# HEXCORE_Schematic.net
KiCad netlist of a schematic drawn in Altium Designer
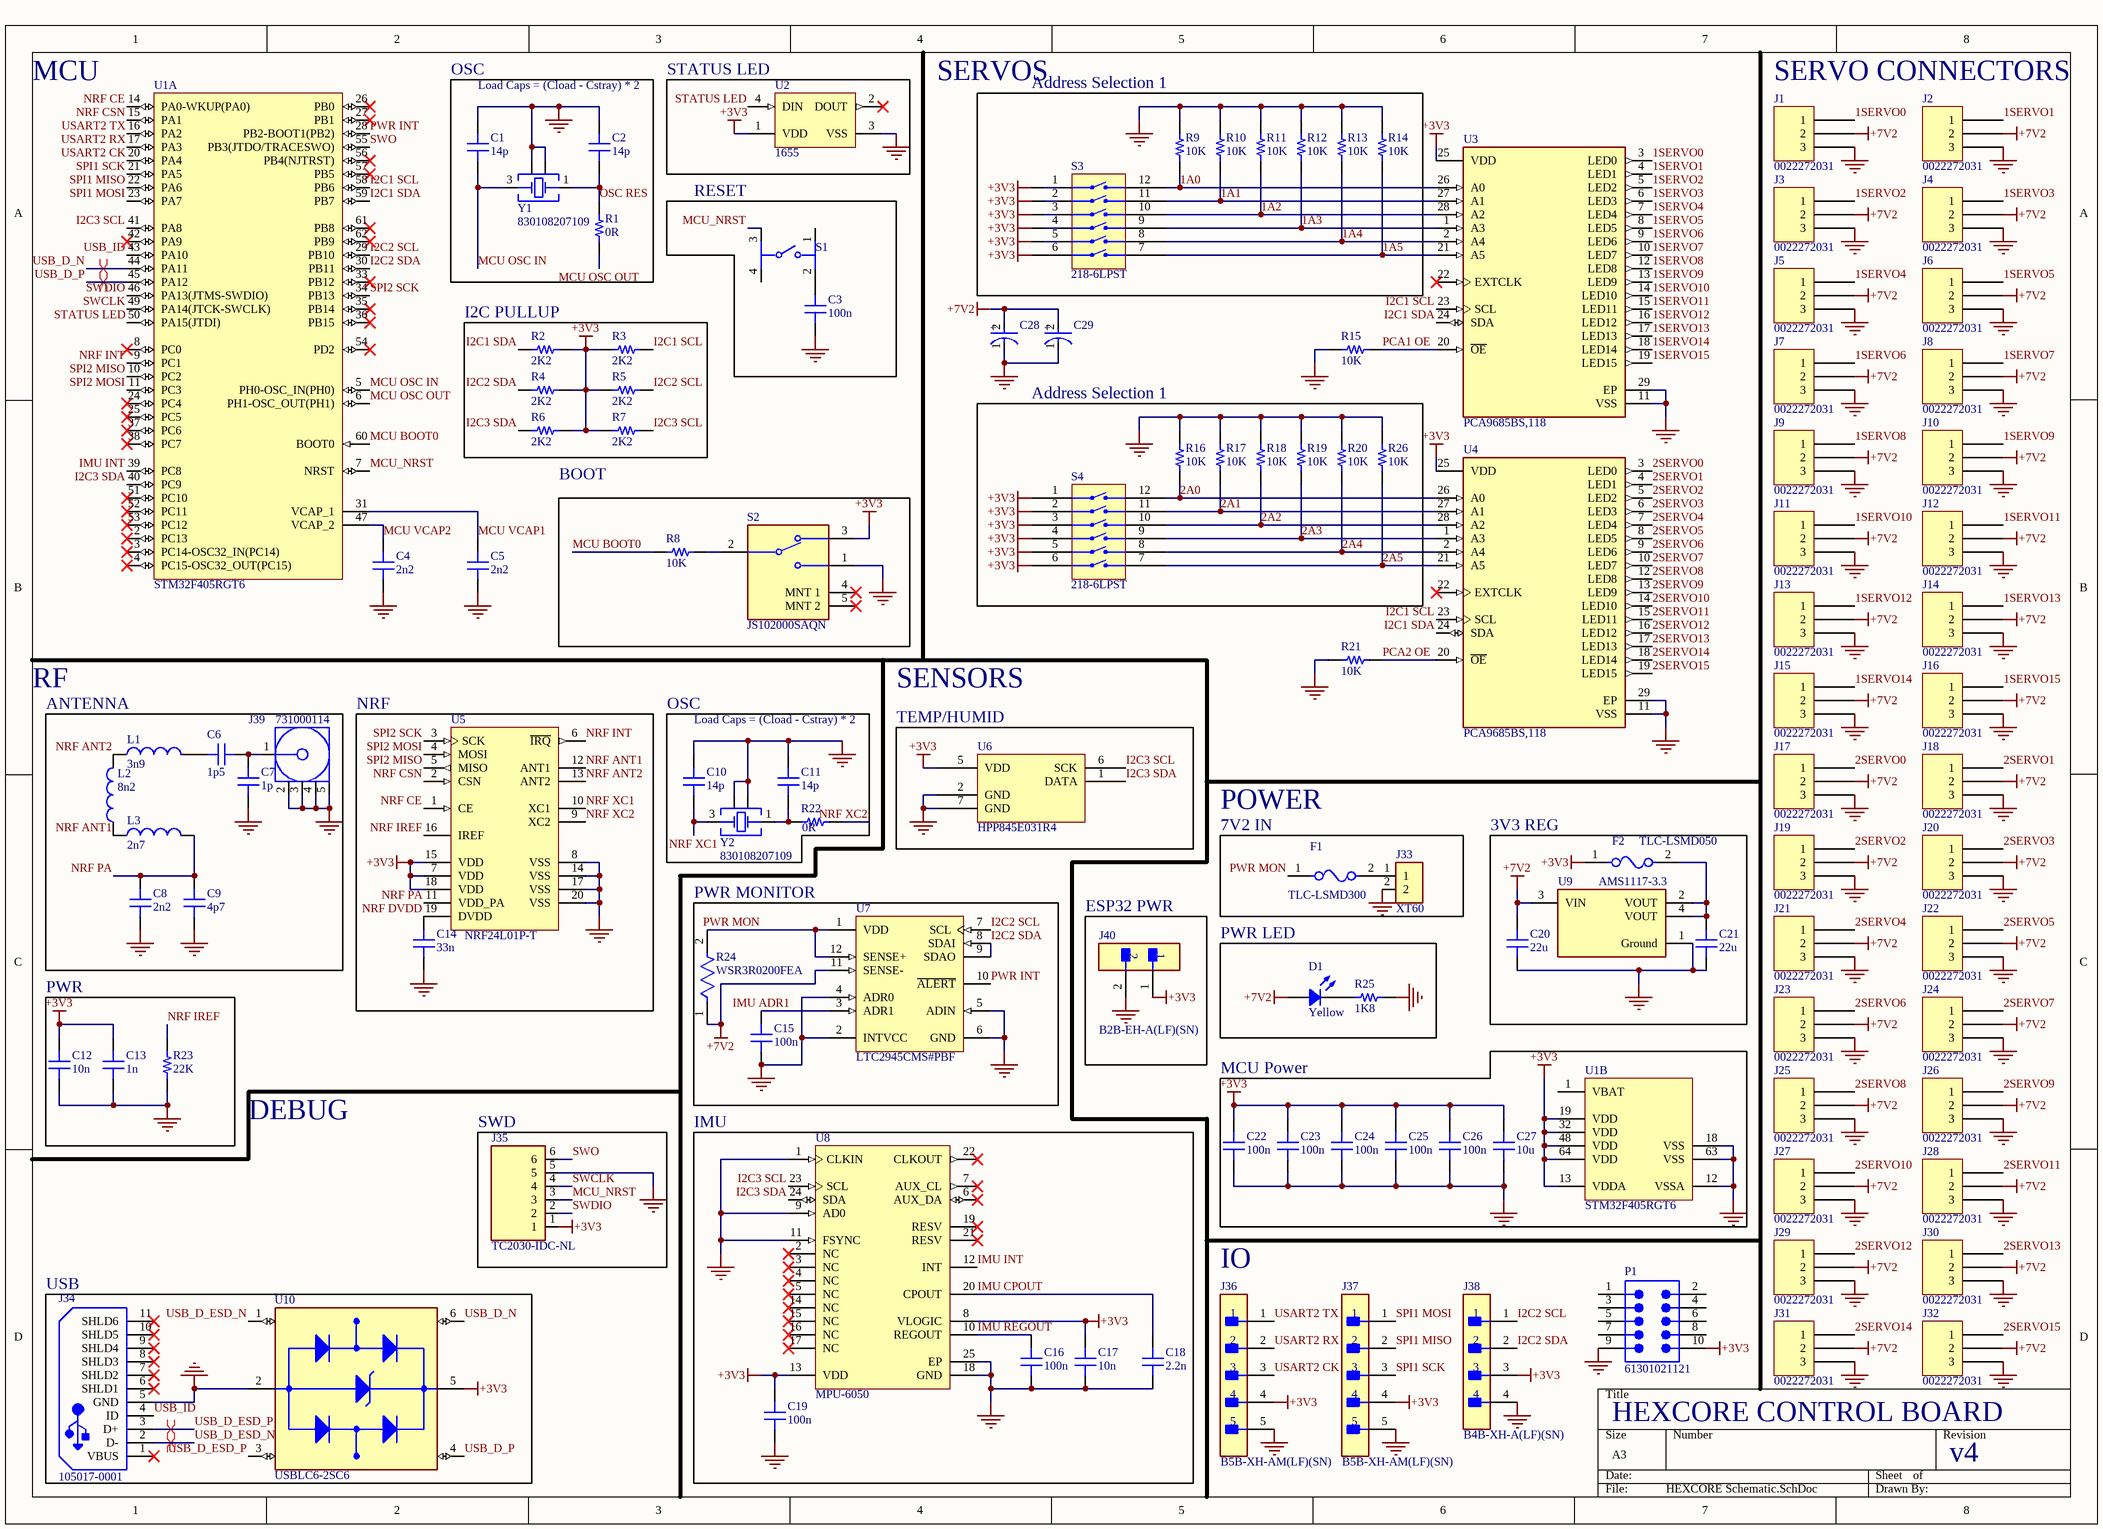
[diagram p0: HEXCORE Schematic.SchDoc]

(export (version "E")
  (design (tool "Eeschema 10.0.6"))
  (components
    (comp (ref "C1")
      (value "14p")
      (footprint "CAP 0402_1005")
      (description "CAP CER 14PF 50V C0G/NP0 0402")
      (fields (field (name "PART NUMBER") "GJM1555C1H140GB01D"))
      (libsource (lib "Celestial Altium Library - altium_library") (part "Capacitor"))
    )
    (comp (ref "C2")
      (value "14p")
      (footprint "CAP 0402_1005")
      (description "CAP CER 14PF 50V C0G/NP0 0402")
      (fields (field (name "PART NUMBER") "GJM1555C1H140GB01D"))
      (libsource (lib "Celestial Altium Library - altium_library") (part "Capacitor"))
    )
    (comp (ref "C3")
      (value "100n")
      (footprint "CAP 0402_1005")
      (description "CAP CER 100NF 10V X7R 0402")
      (fields (field (name "PART NUMBER") "CL05B104KP5VPNC"))
      (libsource (lib "Celestial Altium Library - altium_library") (part "Capacitor"))
    )
    (comp (ref "C4")
      (value "2n2")
      (footprint "CAP 0402_1005")
      (description "CAP CER 0402 2.2NF 25V C0G 5%")
      (fields (field (name "PART NUMBER") "C0402C222J3GEC7867"))
      (libsource (lib "Celestial Altium Library - altium_library") (part "Capacitor"))
    )
    (comp (ref "C5")
      (value "2n2")
      (footprint "CAP 0402_1005")
      (description "CAP CER 0402 2.2NF 25V C0G 5%")
      (fields (field (name "PART NUMBER") "C0402C222J3GEC7867"))
      (libsource (lib "Celestial Altium Library - altium_library") (part "Capacitor"))
    )
    (comp (ref "C6")
      (value "1p5")
      (footprint "CAP 0402_1005")
      (description "CAP CER 0402 10NF 16V X7R 10%")
      (fields (field (name "PART NUMBER") "C0402C103K4REC7867") (field (name "MANUFACTURER") "KEMET"))
      (libsource (lib "Celestial Altium Library - altium_library") (part "Capacitor"))
    )
    (comp (ref "C7")
      (value "1p")
      (footprint "CAP 0402_1005")
      (description "CAP CER 0402 10NF 16V X7R 10%")
      (fields (field (name "PART NUMBER") "C0402C103K4REC7867") (field (name "MANUFACTURER") "KEMET"))
      (libsource (lib "Celestial Altium Library - altium_library") (part "Capacitor"))
    )
    (comp (ref "C8")
      (value "2n2")
      (footprint "CAP 0402_1005")
      (description "CAP CER 0402 10NF 16V X7R 10%")
      (fields (field (name "PART NUMBER") "C0402C103K4REC7867") (field (name "MANUFACTURER") "KEMET"))
      (libsource (lib "Celestial Altium Library - altium_library") (part "Capacitor"))
    )
    (comp (ref "C9")
      (value "4p7")
      (footprint "CAP 0402_1005")
      (description "CAP CER 0402 10NF 16V X7R 10%")
      (fields (field (name "PART NUMBER") "C0402C103K4REC7867") (field (name "MANUFACTURER") "KEMET"))
      (libsource (lib "Celestial Altium Library - altium_library") (part "Capacitor"))
    )
    (comp (ref "C10")
      (value "14p")
      (footprint "CAP 0402_1005")
      (description "CAP CER 14PF 50V C0G/NP0 0402")
      (fields (field (name "PART NUMBER") "GJM1555C1H140GB01D"))
      (libsource (lib "Celestial Altium Library - altium_library") (part "Capacitor"))
    )
    (comp (ref "C11")
      (value "14p")
      (footprint "CAP 0402_1005")
      (description "CAP CER 14PF 50V C0G/NP0 0402")
      (fields (field (name "PART NUMBER") "GJM1555C1H140GB01D"))
      (libsource (lib "Celestial Altium Library - altium_library") (part "Capacitor"))
    )
    (comp (ref "C12")
      (value "10n")
      (footprint "CAP 0402_1005")
      (description "CAP CER 0402 10NF 16V X7R 10%")
      (fields (field (name "PART NUMBER") "C0402C103K4REC7867") (field (name "MANUFACTURER") "KEMET"))
      (libsource (lib "Celestial Altium Library - altium_library") (part "Capacitor"))
    )
    (comp (ref "C13")
      (value "1n")
      (footprint "CAP 0402_1005")
      (description "CAP CER 0402 10NF 16V X7R 10%")
      (fields (field (name "PART NUMBER") "C0402C103K4REC7867") (field (name "MANUFACTURER") "KEMET"))
      (libsource (lib "Celestial Altium Library - altium_library") (part "Capacitor"))
    )
    (comp (ref "C14")
      (value "33n")
      (footprint "CAP 0402_1005")
      (description "CAP CER 33PF 16V X7R 0402")
      (fields (field (name "PART NUMBER") "C0402C330J4RACAUTO") (field (name "MANUFACTURER") "KEMET"))
      (libsource (lib "Celestial Altium Library - altium_library") (part "Capacitor"))
    )
    (comp (ref "C15")
      (value "100n")
      (footprint "CAP 0402_1005")
      (description "CAP CER 100NF 10V X7R 0402")
      (fields (field (name "PART NUMBER") "CL05B104KP5VPNC"))
      (libsource (lib "Celestial Altium Library - altium_library") (part "Capacitor"))
    )
    (comp (ref "C16")
      (value "100n")
      (footprint "CAP 0402_1005")
      (description "CAP CER 100NF 10V X7R 0402")
      (fields (field (name "PART NUMBER") "CL05B104KP5VPNC"))
      (libsource (lib "Celestial Altium Library - altium_library") (part "Capacitor"))
    )
    (comp (ref "C17")
      (value "10n")
      (footprint "CAP 0402_1005")
      (description "CAP CER 0402 10NF 50V X7R 5%")
      (fields (field (name "PART NUMBER") "C0402C103J5RECAUTO"))
      (libsource (lib "Celestial Altium Library - altium_library") (part "Capacitor"))
    )
    (comp (ref "C18")
      (value "2.2n")
      (footprint "CAP 0402_1005")
      (description "CAP CER 0402 2.2NF 25V C0G 5%")
      (fields (field (name "PART NUMBER") "C0402C222J3GEC7867"))
      (libsource (lib "Celestial Altium Library - altium_library") (part "Capacitor"))
    )
    (comp (ref "C19")
      (value "100n")
      (footprint "CAP 0402_1005")
      (description "CAP CER 100NF 10V X7R 0402")
      (fields (field (name "PART NUMBER") "CL05B104KP5VPNC"))
      (libsource (lib "Celestial Altium Library - altium_library") (part "Capacitor"))
    )
    (comp (ref "C20")
      (value "22u")
      (footprint "CAP 0603_1608")
      (description "CAP CER 22UF 10V X5R 0603")
      (fields (field (name "PART NUMBER") "CL10A226MPCNUBE"))
      (libsource (lib "Celestial Altium Library - altium_library") (part "Capacitor"))
    )
    (comp (ref "C21")
      (value "22u")
      (footprint "CAP 0603_1608")
      (description "CAP CER 22UF 10V X5R 0603")
      (fields (field (name "PART NUMBER") "CL10A226MPCNUBE"))
      (libsource (lib "Celestial Altium Library - altium_library") (part "Capacitor"))
    )
    (comp (ref "C22")
      (value "100n")
      (footprint "CAP 0402_1005")
      (description "CAP CER 0402 2.2NF 25V C0G 5%")
      (fields (field (name "PART NUMBER") "C0402C222J3GEC7867"))
      (libsource (lib "Celestial Altium Library - altium_library") (part "Capacitor"))
    )
    (comp (ref "C23")
      (value "100n")
      (footprint "CAP 0402_1005")
      (description "CAP CER 0402 2.2NF 25V C0G 5%")
      (fields (field (name "PART NUMBER") "C0402C222J3GEC7867"))
      (libsource (lib "Celestial Altium Library - altium_library") (part "Capacitor"))
    )
    (comp (ref "C24")
      (value "100n")
      (footprint "CAP 0402_1005")
      (description "CAP CER 0402 2.2NF 25V C0G 5%")
      (fields (field (name "PART NUMBER") "C0402C222J3GEC7867"))
      (libsource (lib "Celestial Altium Library - altium_library") (part "Capacitor"))
    )
    (comp (ref "C25")
      (value "100n")
      (footprint "CAP 0402_1005")
      (description "CAP CER 0402 2.2NF 25V C0G 5%")
      (fields (field (name "PART NUMBER") "C0402C222J3GEC7867"))
      (libsource (lib "Celestial Altium Library - altium_library") (part "Capacitor"))
    )
    (comp (ref "C26")
      (value "100n")
      (footprint "CAP 0402_1005")
      (description "CAP CER 0402 2.2NF 25V C0G 5%")
      (fields (field (name "PART NUMBER") "C0402C222J3GEC7867"))
      (libsource (lib "Celestial Altium Library - altium_library") (part "Capacitor"))
    )
    (comp (ref "C27")
      (value "10u")
      (footprint "CAP 0603_1608")
      (description "CAP CER 10UF 6.3V X5R 0603")
      (fields (field (name "PART NUMBER") "GRM188R60J106ME47D"))
      (libsource (lib "Celestial Altium Library - altium_library") (part "Capacitor"))
    )
    (comp (ref "C28")
      (value "EEE-1AA102P")
      (footprint "FP-SG-MFG")
      (fields (field (name "VOLTAGE") "10V") (field (name "TOLERANCE") "20%"))
      (libsource (lib "Altium Content Vault") (part "a00bbbee19879c290e62620ae7e47b1"))
    )
    (comp (ref "C29")
      (value "EEE-1AA102P")
      (footprint "FP-SG-MFG")
      (fields (field (name "VOLTAGE") "10V") (field (name "TOLERANCE") "20%"))
      (libsource (lib "Altium Content Vault") (part "a00bbbee19879c290e62620ae7e47b1"))
    )
    (comp (ref "D1")
      (value "Yellow")
      (footprint "LED 1206_3216 YELLOW")
      (description "LED YELLOW 1206 SMD")
      (fields (field (name "PART NUMBER") "5990240007F") (field (name "MANUFACTURER") "Dialight"))
      (libsource (lib "Celestial Altium Library - altium_library") (part "LED"))
    )
    (comp (ref "F1")
      (value "TLC-LSMD300")
      (footprint "FP-2920L-MFG")
      (description "PTC RESET FUSE 15V 3A 2920")
      (fields
        (field (name "MANUFACTURER") "Littelfuse")
        (field (name "MANUFACTURER PART NUMBER") "2920L300/15DR")
      )
      (libsource (lib "Altium Content Vault") (part "5bcf9b9f640e542cf0359d10258e979"))
    )
    (comp (ref "F2")
      (value "TLC-LSMD050")
      (footprint "FP-2920L-MFG")
      (description "PTC RESET FUSE 15V 3A 2920")
      (fields
        (field (name "MANUFACTURER") "Littelfuse")
        (field (name "MANUFACTURER PART NUMBER") "2920L300/15DR")
      )
      (libsource (lib "Altium Content Vault") (part "5bcf9b9f640e542cf0359d10258e979"))
    )
    (comp (ref "J1")
      (value "0022272031")
      (footprint "MOLEX KK 0022272031")
      (description "CONN HEADER VERT 3POS 2.54MM")
      (libsource (lib "Celestial Altium Library - altium_library") (part "3 Pin"))
    )
    (comp (ref "J2")
      (value "0022272031")
      (footprint "MOLEX KK 0022272031")
      (description "CONN HEADER VERT 3POS 2.54MM")
      (libsource (lib "Celestial Altium Library - altium_library") (part "3 Pin"))
    )
    (comp (ref "J3")
      (value "0022272031")
      (footprint "MOLEX KK 0022272031")
      (description "CONN HEADER VERT 3POS 2.54MM")
      (libsource (lib "Celestial Altium Library - altium_library") (part "3 Pin"))
    )
    (comp (ref "J4")
      (value "0022272031")
      (footprint "MOLEX KK 0022272031")
      (description "CONN HEADER VERT 3POS 2.54MM")
      (libsource (lib "Celestial Altium Library - altium_library") (part "3 Pin"))
    )
    (comp (ref "J5")
      (value "0022272031")
      (footprint "MOLEX KK 0022272031")
      (description "CONN HEADER VERT 3POS 2.54MM")
      (libsource (lib "Celestial Altium Library - altium_library") (part "3 Pin"))
    )
    (comp (ref "J6")
      (value "0022272031")
      (footprint "MOLEX KK 0022272031")
      (description "CONN HEADER VERT 3POS 2.54MM")
      (libsource (lib "Celestial Altium Library - altium_library") (part "3 Pin"))
    )
    (comp (ref "J7")
      (value "0022272031")
      (footprint "MOLEX KK 0022272031")
      (description "CONN HEADER VERT 3POS 2.54MM")
      (libsource (lib "Celestial Altium Library - altium_library") (part "3 Pin"))
    )
    (comp (ref "J8")
      (value "0022272031")
      (footprint "MOLEX KK 0022272031")
      (description "CONN HEADER VERT 3POS 2.54MM")
      (libsource (lib "Celestial Altium Library - altium_library") (part "3 Pin"))
    )
    (comp (ref "J9")
      (value "0022272031")
      (footprint "MOLEX KK 0022272031")
      (description "CONN HEADER VERT 3POS 2.54MM")
      (libsource (lib "Celestial Altium Library - altium_library") (part "3 Pin"))
    )
    (comp (ref "J10")
      (value "0022272031")
      (footprint "MOLEX KK 0022272031")
      (description "CONN HEADER VERT 3POS 2.54MM")
      (libsource (lib "Celestial Altium Library - altium_library") (part "3 Pin"))
    )
    (comp (ref "J11")
      (value "0022272031")
      (footprint "MOLEX KK 0022272031")
      (description "CONN HEADER VERT 3POS 2.54MM")
      (libsource (lib "Celestial Altium Library - altium_library") (part "3 Pin"))
    )
    (comp (ref "J12")
      (value "0022272031")
      (footprint "MOLEX KK 0022272031")
      (description "CONN HEADER VERT 3POS 2.54MM")
      (libsource (lib "Celestial Altium Library - altium_library") (part "3 Pin"))
    )
    (comp (ref "J13")
      (value "0022272031")
      (footprint "MOLEX KK 0022272031")
      (description "CONN HEADER VERT 3POS 2.54MM")
      (libsource (lib "Celestial Altium Library - altium_library") (part "3 Pin"))
    )
    (comp (ref "J14")
      (value "0022272031")
      (footprint "MOLEX KK 0022272031")
      (description "CONN HEADER VERT 3POS 2.54MM")
      (libsource (lib "Celestial Altium Library - altium_library") (part "3 Pin"))
    )
    (comp (ref "J15")
      (value "0022272031")
      (footprint "MOLEX KK 0022272031")
      (description "CONN HEADER VERT 3POS 2.54MM")
      (libsource (lib "Celestial Altium Library - altium_library") (part "3 Pin"))
    )
    (comp (ref "J16")
      (value "0022272031")
      (footprint "MOLEX KK 0022272031")
      (description "CONN HEADER VERT 3POS 2.54MM")
      (libsource (lib "Celestial Altium Library - altium_library") (part "3 Pin"))
    )
    (comp (ref "J17")
      (value "0022272031")
      (footprint "MOLEX KK 0022272031")
      (description "CONN HEADER VERT 3POS 2.54MM")
      (libsource (lib "Celestial Altium Library - altium_library") (part "3 Pin"))
    )
    (comp (ref "J18")
      (value "0022272031")
      (footprint "MOLEX KK 0022272031")
      (description "CONN HEADER VERT 3POS 2.54MM")
      (libsource (lib "Celestial Altium Library - altium_library") (part "3 Pin"))
    )
    (comp (ref "J19")
      (value "0022272031")
      (footprint "MOLEX KK 0022272031")
      (description "CONN HEADER VERT 3POS 2.54MM")
      (libsource (lib "Celestial Altium Library - altium_library") (part "3 Pin"))
    )
    (comp (ref "J20")
      (value "0022272031")
      (footprint "MOLEX KK 0022272031")
      (description "CONN HEADER VERT 3POS 2.54MM")
      (libsource (lib "Celestial Altium Library - altium_library") (part "3 Pin"))
    )
    (comp (ref "J21")
      (value "0022272031")
      (footprint "MOLEX KK 0022272031")
      (description "CONN HEADER VERT 3POS 2.54MM")
      (libsource (lib "Celestial Altium Library - altium_library") (part "3 Pin"))
    )
    (comp (ref "J22")
      (value "0022272031")
      (footprint "MOLEX KK 0022272031")
      (description "CONN HEADER VERT 3POS 2.54MM")
      (libsource (lib "Celestial Altium Library - altium_library") (part "3 Pin"))
    )
    (comp (ref "J23")
      (value "0022272031")
      (footprint "MOLEX KK 0022272031")
      (description "CONN HEADER VERT 3POS 2.54MM")
      (libsource (lib "Celestial Altium Library - altium_library") (part "3 Pin"))
    )
    (comp (ref "J24")
      (value "0022272031")
      (footprint "MOLEX KK 0022272031")
      (description "CONN HEADER VERT 3POS 2.54MM")
      (libsource (lib "Celestial Altium Library - altium_library") (part "3 Pin"))
    )
    (comp (ref "J25")
      (value "0022272031")
      (footprint "MOLEX KK 0022272031")
      (description "CONN HEADER VERT 3POS 2.54MM")
      (libsource (lib "Celestial Altium Library - altium_library") (part "3 Pin"))
    )
    (comp (ref "J26")
      (value "0022272031")
      (footprint "MOLEX KK 0022272031")
      (description "CONN HEADER VERT 3POS 2.54MM")
      (libsource (lib "Celestial Altium Library - altium_library") (part "3 Pin"))
    )
    (comp (ref "J27")
      (value "0022272031")
      (footprint "MOLEX KK 0022272031")
      (description "CONN HEADER VERT 3POS 2.54MM")
      (libsource (lib "Celestial Altium Library - altium_library") (part "3 Pin"))
    )
    (comp (ref "J28")
      (value "0022272031")
      (footprint "MOLEX KK 0022272031")
      (description "CONN HEADER VERT 3POS 2.54MM")
      (libsource (lib "Celestial Altium Library - altium_library") (part "3 Pin"))
    )
    (comp (ref "J29")
      (value "0022272031")
      (footprint "MOLEX KK 0022272031")
      (description "CONN HEADER VERT 3POS 2.54MM")
      (libsource (lib "Celestial Altium Library - altium_library") (part "3 Pin"))
    )
    (comp (ref "J30")
      (value "0022272031")
      (footprint "MOLEX KK 0022272031")
      (description "CONN HEADER VERT 3POS 2.54MM")
      (libsource (lib "Celestial Altium Library - altium_library") (part "3 Pin"))
    )
    (comp (ref "J31")
      (value "0022272031")
      (footprint "MOLEX KK 0022272031")
      (description "CONN HEADER VERT 3POS 2.54MM")
      (libsource (lib "Celestial Altium Library - altium_library") (part "3 Pin"))
    )
    (comp (ref "J32")
      (value "0022272031")
      (footprint "MOLEX KK 0022272031")
      (description "CONN HEADER VERT 3POS 2.54MM")
      (libsource (lib "Celestial Altium Library - altium_library") (part "3 Pin"))
    )
    (comp (ref "J33")
      (value "XT60")
      (footprint "AMASS_XT60PB-M")
      (description "Power connector; 65A; PIN: 2; Colour: yellow")
      (fields (field (name "MP") "XT60 YELLOW") (field (name "MF") "Pololu"))
      (libsource (lib "XT60_YELLOW") (part "XT60_YELLOW"))
    )
    (comp (ref "J34")
      (value "105017-0001")
      (footprint "USB-MICRO-B_V")
      (fields (field (name "MANUFACTURER") "Molex"))
      (libsource (lib "Altium Content Vault") (part "USB-5-6SHLD"))
    )
    (comp (ref "J35")
      (value "TC2030-IDC-NL")
      (footprint "TAG_TC2030-IDC-NL")
      (description "CABLE ADAPTER 6 POS")
      (libsource (lib "TC2030-IDC-NL") (part "TC2030-IDC-NL"))
    )
    (comp (ref "J36")
      (value "B5B-XH-AM(LF)(SN)")
      (footprint "FP-B5B-XH-AM_LF_SN-MFG")
      (description "CONN HEADER VERT 5POS 2.5MM")
      (libsource (lib "Altium Content Vault") (part "bf93c07fd2649a848d0ec8585582aab"))
    )
    (comp (ref "J37")
      (value "B5B-XH-AM(LF)(SN)")
      (footprint "FP-B5B-XH-AM_LF_SN-MFG")
      (description "CONN HEADER VERT 5POS 2.5MM")
      (libsource (lib "Altium Content Vault") (part "bf93c07fd2649a848d0ec8585582aab"))
    )
    (comp (ref "J38")
      (value "B4B-XH-A(LF)(SN)")
      (footprint "FP-B4B-XH-A_LF_SN-MFG")
      (description "CONN HEADER VERT 4POS 2.5MM")
      (libsource (lib "Altium Content Vault") (part "299a8cea1bdcbc3624fe62c390fa72c"))
    )
    (comp (ref "J39")
      (value "731000114")
      (footprint "MOLX-731000114_V")
      (description "SMA Right-Angle PCB Jack Receptacle, Brass Body, Gold Plated, 50 Ohm, 5-Pin THD, RoHS, Tray")
      (fields (field (name "MANUFACTURER") "Molex"))
      (libsource (lib "Altium Content Vault") (part "CN-S-4F-RF5"))
    )
    (comp (ref "J40")
      (value "B2B-EH-A(LF)(SN)")
      (footprint "FP-B2B-EH-A_LF_SN-MFG")
      (description "CONN HEADER VERT 2POS 2.5MM")
      (libsource (lib "Altium Content Vault") (part "3bc925449376181038e59eaffc5286c"))
    )
    (comp (ref "L1")
      (value "3n9")
      (footprint "WE-TCI_0402")
      (description "744901039 Fixed Ind 3.9NH 340MA 500MOHM Sm")
      (libsource (lib "Altium Content Vault") (part "Inductor - 1"))
    )
    (comp (ref "L2")
      (value "8n2")
      (footprint "WE-TCI_0402")
      (description "744901039 Fixed Ind 3.9NH 340MA 500MOHM Sm")
      (libsource (lib "Altium Content Vault") (part "Inductor - 1"))
    )
    (comp (ref "L3")
      (value "2n7")
      (footprint "WE-TCI_0402")
      (description "744901039 Fixed Ind 3.9NH 340MA 500MOHM Sm")
      (libsource (lib "Altium Content Vault") (part "Inductor - 1"))
    )
    (comp (ref "P1")
      (value "61301021121")
      (footprint "61301021121")
      (libsource (lib "Altium Content Vault") (part "Header_Male_2R_10P"))
    )
    (comp (ref "R1")
      (value "0R")
      (footprint "RES 0402_1005")
      (description "0402 JUMPER ON TAPE AND REEL")
      (fields (field (name "PART NUMBER") "5112"))
      (libsource (lib "Celestial Altium Library - altium_library") (part "Resistor"))
    )
    (comp (ref "R2")
      (value "2K2")
      (footprint "RES 0402_1005")
      (description "RES 10K OHM 0.1% 1/10W 0402")
      (fields (field (name "PART NUMBER") "RP73PF1E10KBTD"))
      (libsource (lib "Celestial Altium Library - altium_library") (part "Resistor"))
    )
    (comp (ref "R3")
      (value "2K2")
      (footprint "RES 0402_1005")
      (description "RES 10K OHM 0.1% 1/10W 0402")
      (fields (field (name "PART NUMBER") "RP73PF1E10KBTD"))
      (libsource (lib "Celestial Altium Library - altium_library") (part "Resistor"))
    )
    (comp (ref "R4")
      (value "2K2")
      (footprint "RES 0402_1005")
      (description "RES 10K OHM 0.1% 1/10W 0402")
      (fields (field (name "PART NUMBER") "RP73PF1E10KBTD"))
      (libsource (lib "Celestial Altium Library - altium_library") (part "Resistor"))
    )
    (comp (ref "R5")
      (value "2K2")
      (footprint "RES 0402_1005")
      (description "RES 10K OHM 0.1% 1/10W 0402")
      (fields (field (name "PART NUMBER") "RP73PF1E10KBTD"))
      (libsource (lib "Celestial Altium Library - altium_library") (part "Resistor"))
    )
    (comp (ref "R6")
      (value "2K2")
      (footprint "RES 0402_1005")
      (description "RES 10K OHM 0.1% 1/10W 0402")
      (fields (field (name "PART NUMBER") "RP73PF1E10KBTD"))
      (libsource (lib "Celestial Altium Library - altium_library") (part "Resistor"))
    )
    (comp (ref "R7")
      (value "2K2")
      (footprint "RES 0402_1005")
      (description "RES 10K OHM 0.1% 1/10W 0402")
      (fields (field (name "PART NUMBER") "RP73PF1E10KBTD"))
      (libsource (lib "Celestial Altium Library - altium_library") (part "Resistor"))
    )
    (comp (ref "R8")
      (value "10K")
      (footprint "RES 0402_1005")
      (description "RES 10K OHM 0.1% 1/10W 0402")
      (fields (field (name "PART NUMBER") "RP73PF1E10KBTD"))
      (libsource (lib "Celestial Altium Library - altium_library") (part "Resistor"))
    )
    (comp (ref "R9")
      (value "10K")
      (footprint "RES 0402_1005")
      (description "RES SMD 10K OHM 0.1% 1/16W 0402")
      (fields (field (name "PART NUMBER") "CPF0402B10KE"))
      (libsource (lib "Celestial Altium Library - altium_library") (part "Resistor"))
    )
    (comp (ref "R10")
      (value "10K")
      (footprint "RES 0402_1005")
      (description "RES SMD 10K OHM 0.1% 1/16W 0402")
      (fields (field (name "PART NUMBER") "CPF0402B10KE"))
      (libsource (lib "Celestial Altium Library - altium_library") (part "Resistor"))
    )
    (comp (ref "R11")
      (value "10K")
      (footprint "RES 0402_1005")
      (description "RES SMD 10K OHM 0.1% 1/16W 0402")
      (fields (field (name "PART NUMBER") "CPF0402B10KE"))
      (libsource (lib "Celestial Altium Library - altium_library") (part "Resistor"))
    )
    (comp (ref "R12")
      (value "10K")
      (footprint "RES 0402_1005")
      (description "RES SMD 10K OHM 0.1% 1/16W 0402")
      (fields (field (name "PART NUMBER") "CPF0402B10KE"))
      (libsource (lib "Celestial Altium Library - altium_library") (part "Resistor"))
    )
    (comp (ref "R13")
      (value "10K")
      (footprint "RES 0402_1005")
      (description "RES SMD 10K OHM 0.1% 1/16W 0402")
      (fields (field (name "PART NUMBER") "CPF0402B10KE"))
      (libsource (lib "Celestial Altium Library - altium_library") (part "Resistor"))
    )
    (comp (ref "R14")
      (value "10K")
      (footprint "RES 0402_1005")
      (description "RES SMD 10K OHM 0.1% 1/16W 0402")
      (fields (field (name "PART NUMBER") "CPF0402B10KE"))
      (libsource (lib "Celestial Altium Library - altium_library") (part "Resistor"))
    )
    (comp (ref "R15")
      (value "10K")
      (footprint "RES 0402_1005")
      (description "RES SMD 10K OHM 0.1% 1/16W 0402")
      (fields (field (name "PART NUMBER") "CPF0402B10KE"))
      (libsource (lib "Celestial Altium Library - altium_library") (part "Resistor"))
    )
    (comp (ref "R16")
      (value "10K")
      (footprint "RES 0402_1005")
      (description "RES SMD 10K OHM 0.1% 1/16W 0402")
      (fields (field (name "PART NUMBER") "CPF0402B10KE"))
      (libsource (lib "Celestial Altium Library - altium_library") (part "Resistor"))
    )
    (comp (ref "R17")
      (value "10K")
      (footprint "RES 0402_1005")
      (description "RES SMD 10K OHM 0.1% 1/16W 0402")
      (fields (field (name "PART NUMBER") "CPF0402B10KE"))
      (libsource (lib "Celestial Altium Library - altium_library") (part "Resistor"))
    )
    (comp (ref "R18")
      (value "10K")
      (footprint "RES 0402_1005")
      (description "RES SMD 10K OHM 0.1% 1/16W 0402")
      (fields (field (name "PART NUMBER") "CPF0402B10KE"))
      (libsource (lib "Celestial Altium Library - altium_library") (part "Resistor"))
    )
    (comp (ref "R19")
      (value "10K")
      (footprint "RES 0402_1005")
      (description "RES SMD 10K OHM 0.1% 1/16W 0402")
      (fields (field (name "PART NUMBER") "CPF0402B10KE"))
      (libsource (lib "Celestial Altium Library - altium_library") (part "Resistor"))
    )
    (comp (ref "R20")
      (value "10K")
      (footprint "RES 0402_1005")
      (description "RES SMD 10K OHM 0.1% 1/16W 0402")
      (fields (field (name "PART NUMBER") "CPF0402B10KE"))
      (libsource (lib "Celestial Altium Library - altium_library") (part "Resistor"))
    )
    (comp (ref "R21")
      (value "10K")
      (footprint "RES 0402_1005")
      (description "RES SMD 10K OHM 0.1% 1/16W 0402")
      (fields (field (name "PART NUMBER") "CPF0402B10KE"))
      (libsource (lib "Celestial Altium Library - altium_library") (part "Resistor"))
    )
    (comp (ref "R22")
      (value "0R")
      (footprint "RES 0402_1005")
      (description "0402 JUMPER ON TAPE AND REEL")
      (fields (field (name "PART NUMBER") "5112"))
      (libsource (lib "Celestial Altium Library - altium_library") (part "Resistor"))
    )
    (comp (ref "R23")
      (value "22K")
      (footprint "RES 0402_1005")
      (description "RES 22.1K OHM 1% 1/16W 0402")
      (fields (field (name "PART NUMBER") "RC0402FR-0722K1L") (field (name "MANUFACTURER") "Yageo"))
      (libsource (lib "Celestial Altium Library - altium_library") (part "Resistor"))
    )
    (comp (ref "R24")
      (value "WSR3R0200FEA")
      (footprint "FP-WSR3-MFG")
      (description "WSR3R0200FEA Res Metal Strip 4527 0.02 Ohm 1% 3W ±75ppm/°C Molded SMD SMD Embossed Plastic T/R")
      (fields (field (name "TOLERANCE") "1%"))
      (libsource (lib "Altium Content Vault") (part "1029c3af85768c4190bb7ad29bc67b5"))
    )
    (comp (ref "R25")
      (value "1K8")
      (footprint "RES 0603_1608")
      (description "RES 1.8K OHM 5% 1/10W 0603")
      (fields
        (field (name "PART NUMBER") "RMCF0603JT1K80")
        (field (name "MANUFACTURER") "Stackpole Electronics Inc")
      )
      (libsource (lib "Celestial Altium Library - altium_library") (part "Resistor"))
    )
    (comp (ref "R26")
      (value "10K")
      (footprint "RES 0402_1005")
      (description "RES SMD 10K OHM 0.1% 1/16W 0402")
      (fields (field (name "PART NUMBER") "CPF0402B10KE"))
      (libsource (lib "Celestial Altium Library - altium_library") (part "Resistor"))
    )
    (comp (ref "S1")
      (value "PTS645SM43SMTR92LFS")
      (footprint "FP-PTS645SM43SMTR92LFS-MFG")
      (description "SWITCH TACTILE SPST-NO 0.05A 12V")
      (libsource (lib "Altium Content Vault") (part "1adf0dd01260c80cf25a44bfd6b99ba"))
    )
    (comp (ref "S2")
      (value "JS102000SAQN")
      (footprint "FP-JS102000SAQN-MFG")
      (description "SWITCH SLIDE SPDT 1MA 5V")
      (libsource (lib "Altium Content Vault") (part "6887e5fe807d9c5c2853bed39bc55bf"))
    )
    (comp (ref "S3")
      (value "218-6LPST")
      (footprint "CTS 218-6LPJ")
      (description "SWITCH SLIDE DIP SPST 25MA 24V")
      (libsource (lib "Celestial Altium Library - altium_library") (part "DIP SW 6P"))
    )
    (comp (ref "S4")
      (value "218-6LPST")
      (footprint "CTS 218-6LPJ")
      (description "SWITCH SLIDE DIP SPST 25MA 24V")
      (libsource (lib "Celestial Altium Library - altium_library") (part "DIP SW 6P"))
    )
    (comp (ref "U1")
      (value "STM32F405RGT6")
      (footprint "STM-LQFP64_N")
      (fields (field (name "MANUFACTURER") "STMicroelectronics"))
      (libsource (lib "Altium Content Vault") (part "MC-ARM-STM32F4X5-SQ64"))
    )
    (comp (ref "U2")
      (value "1655")
      (footprint "ADA-RGB-1655_V")
      (fields (field (name "MANUFACTURER") "Adafruit-Industries-LLC"))
      (libsource (lib "Altium Content Vault") (part "ADA-RGB-1655-4"))
    )
    (comp (ref "U3")
      (value "PCA9685BS,118")
      (footprint "FP-SOT788-1-IPC_B")
      (description "IC LED DRVR LIN DIM 25MA 28HVQFN")
      (libsource (lib "Altium Content Vault") (part "09cd7da67ee680d27754e98215877c2"))
    )
    (comp (ref "U4")
      (value "PCA9685BS,118")
      (footprint "FP-SOT788-1-IPC_B")
      (description "IC LED DRVR LIN DIM 25MA 28HVQFN")
      (libsource (lib "Altium Content Vault") (part "09cd7da67ee680d27754e98215877c2"))
    )
    (comp (ref "U5")
      (value "NRF24L01P-T")
      (footprint "NRSC-QFN-20_L")
      (description "Single Chip Transceiver, 2.4 GHz, 60 mW, 1.9 to 3.6 V, -40 to 85 degC, 20-Pin QFN, RoHS, Tray")
      (fields (field (name "MANUFACTURER") "Nordic Semiconductor"))
      (libsource (lib "Altium Content Vault") (part "NRSC-NRF24L01P-QFN-20"))
    )
    (comp (ref "U6")
      (value "HPP845E031R4")
      (footprint "TE HPP845E031R4")
      (description "SENSOR HUMID/TEMP 3V I2C 2% SMD")
      (libsource (lib "Celestial Altium Library - altium_library") (part "TE HPP845E031R4"))
    )
    (comp (ref "U7")
      (value "LTC2945CMS#PBF")
      (footprint "LT-MS-12_M")
      (description "Wide Range I2C Power Monitor, 12-pin SOP (MS-12), 0 to 70 degC, Pb-Free")
      (fields (field (name "MANUFACTURER") "Linear Technology"))
      (libsource (lib "Altium Content Vault") (part "LT-LTC2945-MS-12"))
    )
    (comp (ref "U8")
      (value "MPU-6050")
      (footprint "IS-QFN-24_V")
      (fields (field (name "MANUFACTURER") "InvenSense"))
      (libsource (lib "Altium Content Vault") (part "IS-MPU-6050-QFN-24"))
    )
    (comp (ref "U9")
      (value "AMS1117-3.3")
      (footprint "FP-AMS1117-IPC_C")
      (description "LDO Voltage Regulators 1A, 3.3V")
      (fields
        (field (name "OCTOPART") "https://octopart.com/ams1117-3.3-advanced+monolithic+systems-25899300")
        (field (name "MANUFACTURER") "Advanced Monolithic Systems")
      )
      (libsource (lib "Altium Content Vault") (part "8bdbb5f8e77002000e30dd2845d0354"))
    )
    (comp (ref "U10")
      (value "USBLC6-2SC6")
      (footprint "SOT95P280X145-6N")
      (description "17V Clamp 5A (8/20Âµs) Ipp Tvs Diode Surface Mount SOT-23-6")
      (fields (field (name "MF") "STMicroelectronics"))
      (libsource (lib "USBLC6-2SC6") (part "USBLC6-2SC6"))
    )
    (comp (ref "Y1")
      (value "830108207109")
      (footprint "WE-XTAL_CFPX-180")
      (description "830108207109 WE-XTAL Quartz Crystal")
      (libsource (lib "Altium Content Vault") (part "WE-XTAL_CFPX-180"))
    )
    (comp (ref "Y2")
      (value "830108207109")
      (footprint "WE-XTAL_CFPX-180")
      (description "830108207109 WE-XTAL Quartz Crystal")
      (libsource (lib "Altium Content Vault") (part "WE-XTAL_CFPX-180"))
    )
  )
  (nets
    (net (code "1") (name "+3V3") (class "Default")
      (node (ref "C12") (pin "2") (pinfunction "2_2") (pintype "passive"))
      (node (ref "C13") (pin "2") (pinfunction "2_2") (pintype "passive"))
      (node (ref "C17") (pin "2") (pinfunction "2_2") (pintype "passive"))
      (node (ref "C19") (pin "2") (pinfunction "2_2") (pintype "passive"))
      (node (ref "C22") (pin "2") (pinfunction "2_2") (pintype "passive"))
      (node (ref "C23") (pin "2") (pinfunction "2_2") (pintype "passive"))
      (node (ref "C24") (pin "2") (pinfunction "2_2") (pintype "passive"))
      (node (ref "C25") (pin "2") (pinfunction "2_2") (pintype "passive"))
      (node (ref "C26") (pin "2") (pinfunction "2_2") (pintype "passive"))
      (node (ref "C27") (pin "2") (pinfunction "2_2") (pintype "passive"))
      (node (ref "F2") (pin "1") (pinfunction "1_1") (pintype "passive"))
      (node (ref "J35") (pin "1") (pinfunction "1_1") (pintype "passive"))
      (node (ref "J36") (pin "4") (pinfunction "4_4") (pintype "passive"))
      (node (ref "J37") (pin "4") (pinfunction "4_4") (pintype "passive"))
      (node (ref "J38") (pin "3") (pinfunction "3_3") (pintype "passive"))
      (node (ref "J40") (pin "1") (pinfunction "1_1") (pintype "passive"))
      (node (ref "P1") (pin "10") (pinfunction "10_10") (pintype "passive"))
      (node (ref "R2") (pin "1") (pinfunction "1_1") (pintype "passive"))
      (node (ref "R3") (pin "2") (pinfunction "2_2") (pintype "passive"))
      (node (ref "R4") (pin "1") (pinfunction "1_1") (pintype "passive"))
      (node (ref "R5") (pin "2") (pinfunction "2_2") (pintype "passive"))
      (node (ref "R6") (pin "1") (pinfunction "1_1") (pintype "passive"))
      (node (ref "R7") (pin "2") (pinfunction "2_2") (pintype "passive"))
      (node (ref "S2") (pin "3") (pinfunction "3_3") (pintype "passive"))
      (node (ref "S3") (pin "1") (pinfunction "GND_1") (pintype "passive"))
      (node (ref "S3") (pin "2") (pinfunction "GND_2") (pintype "passive"))
      (node (ref "S3") (pin "3") (pinfunction "GND_3") (pintype "passive"))
      (node (ref "S3") (pin "4") (pinfunction "GND_4") (pintype "passive"))
      (node (ref "S3") (pin "5") (pinfunction "5_5") (pintype "passive"))
      (node (ref "S3") (pin "6") (pinfunction "6_6") (pintype "passive"))
      (node (ref "S4") (pin "1") (pinfunction "GND_1") (pintype "passive"))
      (node (ref "S4") (pin "2") (pinfunction "GND_2") (pintype "passive"))
      (node (ref "S4") (pin "3") (pinfunction "GND_3") (pintype "passive"))
      (node (ref "S4") (pin "4") (pinfunction "GND_4") (pintype "passive"))
      (node (ref "S4") (pin "5") (pinfunction "5_5") (pintype "passive"))
      (node (ref "S4") (pin "6") (pinfunction "6_6") (pintype "passive"))
      (node (ref "U1") (pin "13") (pinfunction "VDDA_13") (pintype "power_in"))
      (node (ref "U1") (pin "19") (pinfunction "VDD_19") (pintype "power_in"))
      (node (ref "U1") (pin "32") (pinfunction "VDD_32") (pintype "power_in"))
      (node (ref "U1") (pin "48") (pinfunction "VDD_48") (pintype "power_in"))
      (node (ref "U1") (pin "64") (pinfunction "VDD_64") (pintype "power_in"))
      (node (ref "U10") (pin "5") (pinfunction "VBUS_5") (pintype "power_in"))
      (node (ref "U2") (pin "1") (pinfunction "VDD_1") (pintype "power_in"))
      (node (ref "U3") (pin "25") (pinfunction "VDD_25") (pintype "power_in"))
      (node (ref "U4") (pin "25") (pinfunction "VDD_25") (pintype "power_in"))
      (node (ref "U5") (pin "15") (pinfunction "VDD_15") (pintype "power_in"))
      (node (ref "U5") (pin "18") (pinfunction "VDD_18") (pintype "power_in"))
      (node (ref "U5") (pin "7") (pinfunction "VDD_7") (pintype "power_in"))
      (node (ref "U6") (pin "5") (pinfunction "VDD_5") (pintype "passive"))
      (node (ref "U8") (pin "13") (pinfunction "VDD_13") (pintype "power_in"))
      (node (ref "U8") (pin "8") (pinfunction "VLOGIC_8") (pintype "power_in"))
    )
    (net (code "2") (name "+7V2") (class "Default")
      (node (ref "C20") (pin "2") (pinfunction "2_2") (pintype "passive"))
      (node (ref "C28") (pin "2") (pinfunction "A_2") (pintype "passive"))
      (node (ref "C29") (pin "2") (pinfunction "A_2") (pintype "passive"))
      (node (ref "D1") (pin "1") (pinfunction "1_1") (pintype "passive"))
      (node (ref "J1") (pin "2") (pinfunction "2_2") (pintype "passive"))
      (node (ref "J10") (pin "2") (pinfunction "2_2") (pintype "passive"))
      (node (ref "J11") (pin "2") (pinfunction "2_2") (pintype "passive"))
      (node (ref "J12") (pin "2") (pinfunction "2_2") (pintype "passive"))
      (node (ref "J13") (pin "2") (pinfunction "2_2") (pintype "passive"))
      (node (ref "J14") (pin "2") (pinfunction "2_2") (pintype "passive"))
      (node (ref "J15") (pin "2") (pinfunction "2_2") (pintype "passive"))
      (node (ref "J16") (pin "2") (pinfunction "2_2") (pintype "passive"))
      (node (ref "J17") (pin "2") (pinfunction "2_2") (pintype "passive"))
      (node (ref "J18") (pin "2") (pinfunction "2_2") (pintype "passive"))
      (node (ref "J19") (pin "2") (pinfunction "2_2") (pintype "passive"))
      (node (ref "J2") (pin "2") (pinfunction "2_2") (pintype "passive"))
      (node (ref "J20") (pin "2") (pinfunction "2_2") (pintype "passive"))
      (node (ref "J21") (pin "2") (pinfunction "2_2") (pintype "passive"))
      (node (ref "J22") (pin "2") (pinfunction "2_2") (pintype "passive"))
      (node (ref "J23") (pin "2") (pinfunction "2_2") (pintype "passive"))
      (node (ref "J24") (pin "2") (pinfunction "2_2") (pintype "passive"))
      (node (ref "J25") (pin "2") (pinfunction "2_2") (pintype "passive"))
      (node (ref "J26") (pin "2") (pinfunction "2_2") (pintype "passive"))
      (node (ref "J27") (pin "2") (pinfunction "2_2") (pintype "passive"))
      (node (ref "J28") (pin "2") (pinfunction "2_2") (pintype "passive"))
      (node (ref "J29") (pin "2") (pinfunction "2_2") (pintype "passive"))
      (node (ref "J3") (pin "2") (pinfunction "2_2") (pintype "passive"))
      (node (ref "J30") (pin "2") (pinfunction "2_2") (pintype "passive"))
      (node (ref "J31") (pin "2") (pinfunction "2_2") (pintype "passive"))
      (node (ref "J32") (pin "2") (pinfunction "2_2") (pintype "passive"))
      (node (ref "J4") (pin "2") (pinfunction "2_2") (pintype "passive"))
      (node (ref "J5") (pin "2") (pinfunction "2_2") (pintype "passive"))
      (node (ref "J6") (pin "2") (pinfunction "2_2") (pintype "passive"))
      (node (ref "J7") (pin "2") (pinfunction "2_2") (pintype "passive"))
      (node (ref "J8") (pin "2") (pinfunction "2_2") (pintype "passive"))
      (node (ref "J9") (pin "2") (pinfunction "2_2") (pintype "passive"))
      (node (ref "R24") (pin "1") (pinfunction "1_1") (pintype "passive"))
      (node (ref "U7") (pin "11") (pinfunction "SENSE-_11") (pintype "input"))
      (node (ref "U9") (pin "3") (pinfunction "VIN_3") (pintype "power_in"))
    )
    (net (code "3") (name "/1A0") (class "Default")
      (node (ref "R9") (pin "1") (pinfunction "1_1") (pintype "passive"))
      (node (ref "S3") (pin "12") (pinfunction "12_12") (pintype "passive"))
      (node (ref "U3") (pin "26") (pinfunction "A0_26") (pintype "input"))
    )
    (net (code "4") (name "/1A1") (class "Default")
      (node (ref "R10") (pin "1") (pinfunction "1_1") (pintype "passive"))
      (node (ref "S3") (pin "11") (pinfunction "11_11") (pintype "passive"))
      (node (ref "U3") (pin "27") (pinfunction "A1_27") (pintype "input"))
    )
    (net (code "5") (name "/1A2") (class "Default")
      (node (ref "R11") (pin "1") (pinfunction "1_1") (pintype "passive"))
      (node (ref "S3") (pin "10") (pinfunction "10_10") (pintype "passive"))
      (node (ref "U3") (pin "28") (pinfunction "A2_28") (pintype "input"))
    )
    (net (code "6") (name "/1A3") (class "Default")
      (node (ref "R12") (pin "1") (pinfunction "1_1") (pintype "passive"))
      (node (ref "S3") (pin "9") (pinfunction "9_9") (pintype "passive"))
      (node (ref "U3") (pin "1") (pinfunction "A3_1") (pintype "input"))
    )
    (net (code "7") (name "/1A4") (class "Default")
      (node (ref "R13") (pin "1") (pinfunction "1_1") (pintype "passive"))
      (node (ref "S3") (pin "8") (pinfunction "8_8") (pintype "passive"))
      (node (ref "U3") (pin "2") (pinfunction "A4_2") (pintype "input"))
    )
    (net (code "8") (name "/1A5") (class "Default")
      (node (ref "R14") (pin "1") (pinfunction "1_1") (pintype "passive"))
      (node (ref "S3") (pin "7") (pinfunction "7_7") (pintype "passive"))
      (node (ref "U3") (pin "21") (pinfunction "A5_21") (pintype "input"))
    )
    (net (code "9") (name "/1SERVO0") (class "Default")
      (node (ref "J1") (pin "1") (pinfunction "1_1") (pintype "passive"))
      (node (ref "U3") (pin "3") (pinfunction "LED0_3") (pintype "output"))
    )
    (net (code "10") (name "/1SERVO1") (class "Default")
      (node (ref "J2") (pin "1") (pinfunction "1_1") (pintype "passive"))
      (node (ref "U3") (pin "4") (pinfunction "LED1_4") (pintype "output"))
    )
    (net (code "11") (name "/1SERVO2") (class "Default")
      (node (ref "J3") (pin "1") (pinfunction "1_1") (pintype "passive"))
      (node (ref "U3") (pin "5") (pinfunction "LED2_5") (pintype "output"))
    )
    (net (code "12") (name "/1SERVO3") (class "Default")
      (node (ref "J4") (pin "1") (pinfunction "1_1") (pintype "passive"))
      (node (ref "U3") (pin "6") (pinfunction "LED3_6") (pintype "output"))
    )
    (net (code "13") (name "/1SERVO4") (class "Default")
      (node (ref "J5") (pin "1") (pinfunction "1_1") (pintype "passive"))
      (node (ref "U3") (pin "7") (pinfunction "LED4_7") (pintype "output"))
    )
    (net (code "14") (name "/1SERVO5") (class "Default")
      (node (ref "J6") (pin "1") (pinfunction "1_1") (pintype "passive"))
      (node (ref "U3") (pin "8") (pinfunction "LED5_8") (pintype "output"))
    )
    (net (code "15") (name "/1SERVO6") (class "Default")
      (node (ref "J7") (pin "1") (pinfunction "1_1") (pintype "passive"))
      (node (ref "U3") (pin "9") (pinfunction "LED6_9") (pintype "output"))
    )
    (net (code "16") (name "/1SERVO7") (class "Default")
      (node (ref "J8") (pin "1") (pinfunction "1_1") (pintype "passive"))
      (node (ref "U3") (pin "10") (pinfunction "LED7_10") (pintype "output"))
    )
    (net (code "17") (name "/1SERVO8") (class "Default")
      (node (ref "J9") (pin "1") (pinfunction "1_1") (pintype "passive"))
      (node (ref "U3") (pin "12") (pinfunction "LED8_12") (pintype "output"))
    )
    (net (code "18") (name "/1SERVO9") (class "Default")
      (node (ref "J10") (pin "1") (pinfunction "1_1") (pintype "passive"))
      (node (ref "U3") (pin "13") (pinfunction "LED9_13") (pintype "output"))
    )
    (net (code "19") (name "/1SERVO10") (class "Default")
      (node (ref "J11") (pin "1") (pinfunction "1_1") (pintype "passive"))
      (node (ref "U3") (pin "14") (pinfunction "LED10_14") (pintype "output"))
    )
    (net (code "20") (name "/1SERVO11") (class "Default")
      (node (ref "J12") (pin "1") (pinfunction "1_1") (pintype "passive"))
      (node (ref "U3") (pin "15") (pinfunction "LED11_15") (pintype "output"))
    )
    (net (code "21") (name "/1SERVO12") (class "Default")
      (node (ref "J13") (pin "1") (pinfunction "1_1") (pintype "passive"))
      (node (ref "U3") (pin "16") (pinfunction "LED12_16") (pintype "output"))
    )
    (net (code "22") (name "/1SERVO13") (class "Default")
      (node (ref "J14") (pin "1") (pinfunction "1_1") (pintype "passive"))
      (node (ref "U3") (pin "17") (pinfunction "LED13_17") (pintype "output"))
    )
    (net (code "23") (name "/1SERVO14") (class "Default")
      (node (ref "J15") (pin "1") (pinfunction "1_1") (pintype "passive"))
      (node (ref "U3") (pin "18") (pinfunction "LED14_18") (pintype "output"))
    )
    (net (code "24") (name "/1SERVO15") (class "Default")
      (node (ref "J16") (pin "1") (pinfunction "1_1") (pintype "passive"))
      (node (ref "U3") (pin "19") (pinfunction "LED15_19") (pintype "output"))
    )
    (net (code "25") (name "/2A0") (class "Default")
      (node (ref "R16") (pin "1") (pinfunction "1_1") (pintype "passive"))
      (node (ref "S4") (pin "12") (pinfunction "12_12") (pintype "passive"))
      (node (ref "U4") (pin "26") (pinfunction "A0_26") (pintype "input"))
    )
    (net (code "26") (name "/2A1") (class "Default")
      (node (ref "R17") (pin "1") (pinfunction "1_1") (pintype "passive"))
      (node (ref "S4") (pin "11") (pinfunction "11_11") (pintype "passive"))
      (node (ref "U4") (pin "27") (pinfunction "A1_27") (pintype "input"))
    )
    (net (code "27") (name "/2A2") (class "Default")
      (node (ref "R18") (pin "1") (pinfunction "1_1") (pintype "passive"))
      (node (ref "S4") (pin "10") (pinfunction "10_10") (pintype "passive"))
      (node (ref "U4") (pin "28") (pinfunction "A2_28") (pintype "input"))
    )
    (net (code "28") (name "/2A3") (class "Default")
      (node (ref "R19") (pin "1") (pinfunction "1_1") (pintype "passive"))
      (node (ref "S4") (pin "9") (pinfunction "9_9") (pintype "passive"))
      (node (ref "U4") (pin "1") (pinfunction "A3_1") (pintype "input"))
    )
    (net (code "29") (name "/2A4") (class "Default")
      (node (ref "R20") (pin "1") (pinfunction "1_1") (pintype "passive"))
      (node (ref "S4") (pin "8") (pinfunction "8_8") (pintype "passive"))
      (node (ref "U4") (pin "2") (pinfunction "A4_2") (pintype "input"))
    )
    (net (code "30") (name "/2A5") (class "Default")
      (node (ref "R26") (pin "1") (pinfunction "1_1") (pintype "passive"))
      (node (ref "S4") (pin "7") (pinfunction "7_7") (pintype "passive"))
      (node (ref "U4") (pin "21") (pinfunction "A5_21") (pintype "input"))
    )
    (net (code "31") (name "/2SERVO0") (class "Default")
      (node (ref "J17") (pin "1") (pinfunction "1_1") (pintype "passive"))
      (node (ref "U4") (pin "3") (pinfunction "LED0_3") (pintype "output"))
    )
    (net (code "32") (name "/2SERVO1") (class "Default")
      (node (ref "J18") (pin "1") (pinfunction "1_1") (pintype "passive"))
      (node (ref "U4") (pin "4") (pinfunction "LED1_4") (pintype "output"))
    )
    (net (code "33") (name "/2SERVO2") (class "Default")
      (node (ref "J19") (pin "1") (pinfunction "1_1") (pintype "passive"))
      (node (ref "U4") (pin "5") (pinfunction "LED2_5") (pintype "output"))
    )
    (net (code "34") (name "/2SERVO3") (class "Default")
      (node (ref "J20") (pin "1") (pinfunction "1_1") (pintype "passive"))
      (node (ref "U4") (pin "6") (pinfunction "LED3_6") (pintype "output"))
    )
    (net (code "35") (name "/2SERVO4") (class "Default")
      (node (ref "J21") (pin "1") (pinfunction "1_1") (pintype "passive"))
      (node (ref "U4") (pin "7") (pinfunction "LED4_7") (pintype "output"))
    )
    (net (code "36") (name "/2SERVO5") (class "Default")
      (node (ref "J22") (pin "1") (pinfunction "1_1") (pintype "passive"))
      (node (ref "U4") (pin "8") (pinfunction "LED5_8") (pintype "output"))
    )
    (net (code "37") (name "/2SERVO6") (class "Default")
      (node (ref "J23") (pin "1") (pinfunction "1_1") (pintype "passive"))
      (node (ref "U4") (pin "9") (pinfunction "LED6_9") (pintype "output"))
    )
    (net (code "38") (name "/2SERVO7") (class "Default")
      (node (ref "J24") (pin "1") (pinfunction "1_1") (pintype "passive"))
      (node (ref "U4") (pin "10") (pinfunction "LED7_10") (pintype "output"))
    )
    (net (code "39") (name "/2SERVO8") (class "Default")
      (node (ref "J25") (pin "1") (pinfunction "1_1") (pintype "passive"))
      (node (ref "U4") (pin "12") (pinfunction "LED8_12") (pintype "output"))
    )
    (net (code "40") (name "/2SERVO9") (class "Default")
      (node (ref "J26") (pin "1") (pinfunction "1_1") (pintype "passive"))
      (node (ref "U4") (pin "13") (pinfunction "LED9_13") (pintype "output"))
    )
    (net (code "41") (name "/2SERVO10") (class "Default")
      (node (ref "J27") (pin "1") (pinfunction "1_1") (pintype "passive"))
      (node (ref "U4") (pin "14") (pinfunction "LED10_14") (pintype "output"))
    )
    (net (code "42") (name "/2SERVO11") (class "Default")
      (node (ref "J28") (pin "1") (pinfunction "1_1") (pintype "passive"))
      (node (ref "U4") (pin "15") (pinfunction "LED11_15") (pintype "output"))
    )
    (net (code "43") (name "/2SERVO12") (class "Default")
      (node (ref "J29") (pin "1") (pinfunction "1_1") (pintype "passive"))
      (node (ref "U4") (pin "16") (pinfunction "LED12_16") (pintype "output"))
    )
    (net (code "44") (name "/2SERVO13") (class "Default")
      (node (ref "J30") (pin "1") (pinfunction "1_1") (pintype "passive"))
      (node (ref "U4") (pin "17") (pinfunction "LED13_17") (pintype "output"))
    )
    (net (code "45") (name "/2SERVO14") (class "Default")
      (node (ref "J31") (pin "1") (pinfunction "1_1") (pintype "passive"))
      (node (ref "U4") (pin "18") (pinfunction "LED14_18") (pintype "output"))
    )
    (net (code "46") (name "/2SERVO15") (class "Default")
      (node (ref "J32") (pin "1") (pinfunction "1_1") (pintype "passive"))
      (node (ref "U4") (pin "19") (pinfunction "LED15_19") (pintype "output"))
    )
    (net (code "47") (name "/I2C1 SCL") (class "Default")
      (node (ref "R3") (pin "1") (pinfunction "1_1") (pintype "passive"))
      (node (ref "U1") (pin "58") (pinfunction "PB6_58") (pintype "bidirectional"))
      (node (ref "U3") (pin "23") (pinfunction "SCL_23") (pintype "input"))
      (node (ref "U4") (pin "23") (pinfunction "SCL_23") (pintype "input"))
    )
    (net (code "48") (name "/I2C1 SDA") (class "Default")
      (node (ref "R2") (pin "2") (pinfunction "2_2") (pintype "passive"))
      (node (ref "U1") (pin "59") (pinfunction "PB7_59") (pintype "bidirectional"))
      (node (ref "U3") (pin "24") (pinfunction "SDA_24") (pintype "bidirectional"))
      (node (ref "U4") (pin "24") (pinfunction "SDA_24") (pintype "bidirectional"))
    )
    (net (code "49") (name "/I2C2 SCL") (class "Default")
      (node (ref "J38") (pin "1") (pinfunction "1_1") (pintype "passive"))
      (node (ref "R5") (pin "1") (pinfunction "1_1") (pintype "passive"))
      (node (ref "U1") (pin "29") (pinfunction "PB10_29") (pintype "bidirectional"))
      (node (ref "U7") (pin "7") (pinfunction "SCL_7") (pintype "input"))
    )
    (net (code "50") (name "/I2C2 SDA") (class "Default")
      (node (ref "J38") (pin "2") (pinfunction "2_2") (pintype "passive"))
      (node (ref "R4") (pin "2") (pinfunction "2_2") (pintype "passive"))
      (node (ref "U1") (pin "30") (pinfunction "PB11_30") (pintype "bidirectional"))
      (node (ref "U7") (pin "8") (pinfunction "SDAI_8") (pintype "input"))
      (node (ref "U7") (pin "9") (pinfunction "SDAO_9") (pintype "open_collector"))
    )
    (net (code "51") (name "/I2C3 SCL") (class "Default")
      (node (ref "R7") (pin "1") (pinfunction "1_1") (pintype "passive"))
      (node (ref "U1") (pin "41") (pinfunction "PA8_41") (pintype "bidirectional"))
      (node (ref "U6") (pin "6") (pinfunction "SCK_6") (pintype "passive"))
      (node (ref "U8") (pin "23") (pinfunction "SCL_23") (pintype "input"))
    )
    (net (code "52") (name "/I2C3 SDA") (class "Default")
      (node (ref "R6") (pin "2") (pinfunction "2_2") (pintype "passive"))
      (node (ref "U1") (pin "40") (pinfunction "PC9_40") (pintype "bidirectional"))
      (node (ref "U6") (pin "1") (pinfunction "DATA_1") (pintype "passive"))
      (node (ref "U8") (pin "24") (pinfunction "SDA_24") (pintype "bidirectional"))
    )
    (net (code "53") (name "/IMU ADR1") (class "Default")
      (node (ref "C15") (pin "2") (pinfunction "2_2") (pintype "passive"))
      (node (ref "U7") (pin "3") (pinfunction "ADR1_3") (pintype "input"))
    )
    (net (code "54") (name "/IMU CPOUT") (class "Default")
      (node (ref "C18") (pin "2") (pinfunction "2_2") (pintype "passive"))
      (node (ref "U8") (pin "20") (pinfunction "CPOUT_20") (pintype "passive"))
    )
    (net (code "55") (name "/IMU INT") (class "Default")
      (node (ref "U1") (pin "39") (pinfunction "PC8_39") (pintype "bidirectional"))
      (node (ref "U8") (pin "12") (pinfunction "INT_12") (pintype "open_collector"))
    )
    (net (code "56") (name "/IMU REGOUT") (class "Default")
      (node (ref "C16") (pin "2") (pinfunction "2_2") (pintype "passive"))
      (node (ref "U8") (pin "10") (pinfunction "REGOUT_10") (pintype "passive"))
    )
    (net (code "57") (name "/MCU BOOT0") (class "Default")
      (node (ref "R8") (pin "1") (pinfunction "1_1") (pintype "passive"))
      (node (ref "U1") (pin "60") (pinfunction "BOOT0_60") (pintype "input"))
    )
    (net (code "58") (name "/MCU OSC IN") (class "Default")
      (node (ref "C1") (pin "1") (pinfunction "1_1") (pintype "passive"))
      (node (ref "U1") (pin "5") (pinfunction "PH0-OSC_IN(PH0)_5") (pintype "bidirectional"))
      (node (ref "Y1") (pin "3") (pinfunction "Crystal_3") (pintype "passive"))
    )
    (net (code "59") (name "/MCU OSC OUT") (class "Default")
      (node (ref "R1") (pin "1") (pinfunction "1_1") (pintype "passive"))
      (node (ref "U1") (pin "6") (pinfunction "PH1-OSC_OUT(PH1)_6") (pintype "bidirectional"))
    )
    (net (code "60") (name "/MCU VCAP1") (class "Default")
      (node (ref "C5") (pin "2") (pinfunction "2_2") (pintype "passive"))
      (node (ref "U1") (pin "31") (pinfunction "VCAP_1_31") (pintype "power_in"))
    )
    (net (code "61") (name "/MCU VCAP2") (class "Default")
      (node (ref "C4") (pin "2") (pinfunction "2_2") (pintype "passive"))
      (node (ref "U1") (pin "47") (pinfunction "VCAP_2_47") (pintype "power_in"))
    )
    (net (code "62") (name "/MCU_NRST") (class "Default")
      (node (ref "J35") (pin "3") (pinfunction "3_3") (pintype "passive"))
      (node (ref "S1") (pin "3") (pinfunction "3_3") (pintype "passive"))
      (node (ref "U1") (pin "7") (pinfunction "NRST_7") (pintype "bidirectional"))
    )
    (net (code "63") (name "/NRF ANT1") (class "Default")
      (node (ref "L2") (pin "1") (pinfunction "1_1") (pintype "passive"))
      (node (ref "L3") (pin "1") (pinfunction "1_1") (pintype "passive"))
      (node (ref "U5") (pin "12") (pinfunction "ANT1_12") (pintype "passive"))
    )
    (net (code "64") (name "/NRF ANT2") (class "Default")
      (node (ref "L1") (pin "1") (pinfunction "1_1") (pintype "passive"))
      (node (ref "L2") (pin "2") (pinfunction "2_2") (pintype "passive"))
      (node (ref "U5") (pin "13") (pinfunction "ANT2_13") (pintype "passive"))
    )
    (net (code "65") (name "/NRF CE") (class "Default")
      (node (ref "U1") (pin "14") (pinfunction "PA0-WKUP(PA0)_14") (pintype "bidirectional"))
      (node (ref "U5") (pin "1") (pinfunction "CE_1") (pintype "input"))
    )
    (net (code "66") (name "/NRF CSN") (class "Default")
      (node (ref "U1") (pin "15") (pinfunction "PA1_15") (pintype "bidirectional"))
      (node (ref "U5") (pin "2") (pinfunction "CSN_2") (pintype "input"))
    )
    (net (code "67") (name "/NRF DVDD") (class "Default")
      (node (ref "C14") (pin "2") (pinfunction "2_2") (pintype "passive"))
      (node (ref "U5") (pin "19") (pinfunction "DVDD_19") (pintype "power_in"))
    )
    (net (code "68") (name "/NRF INT") (class "Default")
      (node (ref "U1") (pin "9") (pinfunction "PC1_9") (pintype "bidirectional"))
      (node (ref "U5") (pin "6") (pinfunction "~{IRQ}_6") (pintype "output"))
    )
    (net (code "69") (name "/NRF IREF") (class "Default")
      (node (ref "R23") (pin "1") (pinfunction "1_1") (pintype "passive"))
      (node (ref "U5") (pin "16") (pinfunction "IREF_16") (pintype "passive"))
    )
    (net (code "70") (name "/NRF PA") (class "Default")
      (node (ref "C8") (pin "2") (pinfunction "2_2") (pintype "passive"))
      (node (ref "C9") (pin "2") (pinfunction "2_2") (pintype "passive"))
      (node (ref "L3") (pin "2") (pinfunction "2_2") (pintype "passive"))
      (node (ref "U5") (pin "11") (pinfunction "VDD_PA_11") (pintype "power_in"))
    )
    (net (code "71") (name "/NRF XC1") (class "Default")
      (node (ref "C10") (pin "1") (pinfunction "1_1") (pintype "passive"))
      (node (ref "U5") (pin "10") (pinfunction "XC1_10") (pintype "passive"))
      (node (ref "Y2") (pin "3") (pinfunction "Crystal_3") (pintype "passive"))
    )
    (net (code "72") (name "/NRF XC2") (class "Default")
      (node (ref "R22") (pin "2") (pinfunction "2_2") (pintype "passive"))
      (node (ref "U5") (pin "9") (pinfunction "XC2_9") (pintype "passive"))
    )
    (net (code "73") (name "/OSC RES") (class "Default")
      (node (ref "C2") (pin "1") (pinfunction "1_1") (pintype "passive"))
      (node (ref "R1") (pin "2") (pinfunction "2_2") (pintype "passive"))
      (node (ref "Y1") (pin "1") (pinfunction "Crystal_1") (pintype "passive"))
    )
    (net (code "74") (name "/PCA1 OE") (class "Default")
      (node (ref "R15") (pin "1") (pinfunction "1_1") (pintype "passive"))
      (node (ref "U3") (pin "20") (pinfunction "~{OE}_20") (pintype "input"))
    )
    (net (code "75") (name "/PCA2 OE") (class "Default")
      (node (ref "R21") (pin "1") (pinfunction "1_1") (pintype "passive"))
      (node (ref "U4") (pin "20") (pinfunction "~{OE}_20") (pintype "input"))
    )
    (net (code "76") (name "/PWR INT") (class "Default")
      (node (ref "U1") (pin "28") (pinfunction "PB2-BOOT1(PB2)_28") (pintype "bidirectional"))
      (node (ref "U7") (pin "10") (pinfunction "~{ALERT}_10") (pintype "open_collector"))
    )
    (net (code "77") (name "/PWR MON") (class "Default")
      (node (ref "F1") (pin "1") (pinfunction "1_1") (pintype "passive"))
      (node (ref "R24") (pin "2") (pinfunction "2_2") (pintype "passive"))
      (node (ref "U7") (pin "1") (pinfunction "VDD_1") (pintype "power_in"))
      (node (ref "U7") (pin "12") (pinfunction "SENSE+_12") (pintype "input"))
    )
    (net (code "78") (name "/SPI1 MISO") (class "Default")
      (node (ref "J37") (pin "2") (pinfunction "2_2") (pintype "passive"))
      (node (ref "U1") (pin "22") (pinfunction "PA6_22") (pintype "bidirectional"))
    )
    (net (code "79") (name "/SPI1 MOSI") (class "Default")
      (node (ref "J37") (pin "1") (pinfunction "1_1") (pintype "passive"))
      (node (ref "U1") (pin "23") (pinfunction "PA7_23") (pintype "bidirectional"))
    )
    (net (code "80") (name "/SPI1 SCK") (class "Default")
      (node (ref "J37") (pin "3") (pinfunction "3_3") (pintype "passive"))
      (node (ref "U1") (pin "21") (pinfunction "PA5_21") (pintype "bidirectional"))
    )
    (net (code "81") (name "/SPI2 MISO") (class "Default")
      (node (ref "U1") (pin "10") (pinfunction "PC2_10") (pintype "bidirectional"))
      (node (ref "U5") (pin "5") (pinfunction "MISO_5") (pintype "output"))
    )
    (net (code "82") (name "/SPI2 MOSI") (class "Default")
      (node (ref "U1") (pin "11") (pinfunction "PC3_11") (pintype "bidirectional"))
      (node (ref "U5") (pin "4") (pinfunction "MOSI_4") (pintype "input"))
    )
    (net (code "83") (name "/SPI2 SCK") (class "Default")
      (node (ref "U1") (pin "34") (pinfunction "PB13_34") (pintype "bidirectional"))
      (node (ref "U5") (pin "3") (pinfunction "SCK_3") (pintype "input"))
    )
    (net (code "84") (name "/STATUS LED") (class "Default")
      (node (ref "U1") (pin "50") (pinfunction "PA15(JTDI)_50") (pintype "bidirectional"))
      (node (ref "U2") (pin "4") (pinfunction "DIN_4") (pintype "input"))
    )
    (net (code "85") (name "/SWCLK") (class "Default")
      (node (ref "J35") (pin "4") (pinfunction "4_4") (pintype "passive"))
      (node (ref "U1") (pin "49") (pinfunction "PA14(JTCK-SWCLK)_49") (pintype "bidirectional"))
    )
    (net (code "86") (name "/SWDIO") (class "Default")
      (node (ref "J35") (pin "2") (pinfunction "2_2") (pintype "passive"))
      (node (ref "U1") (pin "46") (pinfunction "PA13(JTMS-SWDIO)_46") (pintype "bidirectional"))
    )
    (net (code "87") (name "/SWO") (class "Default")
      (node (ref "J35") (pin "6") (pinfunction "6_6") (pintype "passive"))
      (node (ref "U1") (pin "55") (pinfunction "PB3(JTDO/TRACESWO)_55") (pintype "bidirectional"))
    )
    (net (code "88") (name "/USART2 CK") (class "Default")
      (node (ref "J36") (pin "3") (pinfunction "3_3") (pintype "passive"))
      (node (ref "U1") (pin "20") (pinfunction "PA4_20") (pintype "bidirectional"))
    )
    (net (code "89") (name "/USART2 RX") (class "Default")
      (node (ref "J36") (pin "2") (pinfunction "2_2") (pintype "passive"))
      (node (ref "U1") (pin "17") (pinfunction "PA3_17") (pintype "bidirectional"))
    )
    (net (code "90") (name "/USART2 TX") (class "Default")
      (node (ref "J36") (pin "1") (pinfunction "1_1") (pintype "passive"))
      (node (ref "U1") (pin "16") (pinfunction "PA2_16") (pintype "bidirectional"))
    )
    (net (code "91") (name "/USB_D_ESD_N") (class "Default")
      (node (ref "J34") (pin "2") (pinfunction "D-_2") (pintype "passive"))
      (node (ref "U10") (pin "1") (pinfunction "I/O1_IN_1") (pintype "bidirectional"))
    )
    (net (code "92") (name "/USB_D_ESD_P") (class "Default")
      (node (ref "J34") (pin "3") (pinfunction "D+_3") (pintype "passive"))
      (node (ref "U10") (pin "3") (pinfunction "I/O2_IN_3") (pintype "bidirectional"))
    )
    (net (code "93") (name "/USB_D_N") (class "Default")
      (node (ref "U1") (pin "44") (pinfunction "PA11_44") (pintype "bidirectional"))
      (node (ref "U10") (pin "6") (pinfunction "I/O1_OUT_6") (pintype "bidirectional"))
    )
    (net (code "94") (name "/USB_D_P") (class "Default")
      (node (ref "U1") (pin "45") (pinfunction "PA12_45") (pintype "bidirectional"))
      (node (ref "U10") (pin "4") (pinfunction "I/O2_OUT_4") (pintype "bidirectional"))
    )
    (net (code "95") (name "/USB_ID") (class "Default")
      (node (ref "J34") (pin "4") (pinfunction "ID_4") (pintype "passive"))
      (node (ref "U1") (pin "43") (pinfunction "PA10_43") (pintype "bidirectional"))
    )
    (net (code "96") (name "GND") (class "Default")
      (node (ref "C1") (pin "2") (pinfunction "2_2") (pintype "passive"))
      (node (ref "C10") (pin "2") (pinfunction "2_2") (pintype "passive"))
      (node (ref "C11") (pin "2") (pinfunction "2_2") (pintype "passive"))
      (node (ref "C12") (pin "1") (pinfunction "1_1") (pintype "passive"))
      (node (ref "C13") (pin "1") (pinfunction "1_1") (pintype "passive"))
      (node (ref "C14") (pin "1") (pinfunction "1_1") (pintype "passive"))
      (node (ref "C15") (pin "1") (pinfunction "1_1") (pintype "passive"))
      (node (ref "C16") (pin "1") (pinfunction "1_1") (pintype "passive"))
      (node (ref "C17") (pin "1") (pinfunction "1_1") (pintype "passive"))
      (node (ref "C18") (pin "1") (pinfunction "1_1") (pintype "passive"))
      (node (ref "C19") (pin "1") (pinfunction "1_1") (pintype "passive"))
      (node (ref "C2") (pin "2") (pinfunction "2_2") (pintype "passive"))
      (node (ref "C20") (pin "1") (pinfunction "1_1") (pintype "passive"))
      (node (ref "C21") (pin "1") (pinfunction "1_1") (pintype "passive"))
      (node (ref "C22") (pin "1") (pinfunction "1_1") (pintype "passive"))
      (node (ref "C23") (pin "1") (pinfunction "1_1") (pintype "passive"))
      (node (ref "C24") (pin "1") (pinfunction "1_1") (pintype "passive"))
      (node (ref "C25") (pin "1") (pinfunction "1_1") (pintype "passive"))
      (node (ref "C26") (pin "1") (pinfunction "1_1") (pintype "passive"))
      (node (ref "C27") (pin "1") (pinfunction "1_1") (pintype "passive"))
      (node (ref "C28") (pin "1") (pinfunction "C_1") (pintype "passive"))
      (node (ref "C29") (pin "1") (pinfunction "C_1") (pintype "passive"))
      (node (ref "C3") (pin "2") (pinfunction "2_2") (pintype "passive"))
      (node (ref "C4") (pin "1") (pinfunction "1_1") (pintype "passive"))
      (node (ref "C5") (pin "1") (pinfunction "1_1") (pintype "passive"))
      (node (ref "C7") (pin "1") (pinfunction "1_1") (pintype "passive"))
      (node (ref "C8") (pin "1") (pinfunction "1_1") (pintype "passive"))
      (node (ref "C9") (pin "1") (pinfunction "1_1") (pintype "passive"))
      (node (ref "J1") (pin "3") (pinfunction "3_3") (pintype "passive"))
      (node (ref "J10") (pin "3") (pinfunction "3_3") (pintype "passive"))
      (node (ref "J11") (pin "3") (pinfunction "3_3") (pintype "passive"))
      (node (ref "J12") (pin "3") (pinfunction "3_3") (pintype "passive"))
      (node (ref "J13") (pin "3") (pinfunction "3_3") (pintype "passive"))
      (node (ref "J14") (pin "3") (pinfunction "3_3") (pintype "passive"))
      (node (ref "J15") (pin "3") (pinfunction "3_3") (pintype "passive"))
      (node (ref "J16") (pin "3") (pinfunction "3_3") (pintype "passive"))
      (node (ref "J17") (pin "3") (pinfunction "3_3") (pintype "passive"))
      (node (ref "J18") (pin "3") (pinfunction "3_3") (pintype "passive"))
      (node (ref "J19") (pin "3") (pinfunction "3_3") (pintype "passive"))
      (node (ref "J2") (pin "3") (pinfunction "3_3") (pintype "passive"))
      (node (ref "J20") (pin "3") (pinfunction "3_3") (pintype "passive"))
      (node (ref "J21") (pin "3") (pinfunction "3_3") (pintype "passive"))
      (node (ref "J22") (pin "3") (pinfunction "3_3") (pintype "passive"))
      (node (ref "J23") (pin "3") (pinfunction "3_3") (pintype "passive"))
      (node (ref "J24") (pin "3") (pinfunction "3_3") (pintype "passive"))
      (node (ref "J25") (pin "3") (pinfunction "3_3") (pintype "passive"))
      (node (ref "J26") (pin "3") (pinfunction "3_3") (pintype "passive"))
      (node (ref "J27") (pin "3") (pinfunction "3_3") (pintype "passive"))
      (node (ref "J28") (pin "3") (pinfunction "3_3") (pintype "passive"))
      (node (ref "J29") (pin "3") (pinfunction "3_3") (pintype "passive"))
      (node (ref "J3") (pin "3") (pinfunction "3_3") (pintype "passive"))
      (node (ref "J30") (pin "3") (pinfunction "3_3") (pintype "passive"))
      (node (ref "J31") (pin "3") (pinfunction "3_3") (pintype "passive"))
      (node (ref "J32") (pin "3") (pinfunction "3_3") (pintype "passive"))
      (node (ref "J33") (pin "2") (pinfunction "2_2") (pintype "passive"))
      (node (ref "J34") (pin "5") (pinfunction "GND_5") (pintype "passive"))
      (node (ref "J35") (pin "5") (pinfunction "5_5") (pintype "passive"))
      (node (ref "J36") (pin "5") (pinfunction "5_5") (pintype "passive"))
      (node (ref "J37") (pin "5") (pinfunction "5_5") (pintype "passive"))
      (node (ref "J38") (pin "4") (pinfunction "4_4") (pintype "passive"))
      (node (ref "J39") (pin "2") (pinfunction "2_2") (pintype "passive"))
      (node (ref "J39") (pin "3") (pinfunction "3_3") (pintype "passive"))
      (node (ref "J39") (pin "4") (pinfunction "4_4") (pintype "passive"))
      (node (ref "J39") (pin "5") (pinfunction "5_5") (pintype "passive"))
      (node (ref "J4") (pin "3") (pinfunction "3_3") (pintype "passive"))
      (node (ref "J40") (pin "2") (pinfunction "2_2") (pintype "passive"))
      (node (ref "J5") (pin "3") (pinfunction "3_3") (pintype "passive"))
      (node (ref "J6") (pin "3") (pinfunction "3_3") (pintype "passive"))
      (node (ref "J7") (pin "3") (pinfunction "3_3") (pintype "passive"))
      (node (ref "J8") (pin "3") (pinfunction "3_3") (pintype "passive"))
      (node (ref "J9") (pin "3") (pinfunction "3_3") (pintype "passive"))
      (node (ref "P1") (pin "9") (pinfunction "9_9") (pintype "passive"))
      (node (ref "R10") (pin "2") (pinfunction "2_2") (pintype "passive"))
      (node (ref "R11") (pin "2") (pinfunction "2_2") (pintype "passive"))
      (node (ref "R12") (pin "2") (pinfunction "2_2") (pintype "passive"))
      (node (ref "R13") (pin "2") (pinfunction "2_2") (pintype "passive"))
      (node (ref "R14") (pin "2") (pinfunction "2_2") (pintype "passive"))
      (node (ref "R15") (pin "2") (pinfunction "2_2") (pintype "passive"))
      (node (ref "R16") (pin "2") (pinfunction "2_2") (pintype "passive"))
      (node (ref "R17") (pin "2") (pinfunction "2_2") (pintype "passive"))
      (node (ref "R18") (pin "2") (pinfunction "2_2") (pintype "passive"))
      (node (ref "R19") (pin "2") (pinfunction "2_2") (pintype "passive"))
      (node (ref "R20") (pin "2") (pinfunction "2_2") (pintype "passive"))
      (node (ref "R21") (pin "2") (pinfunction "2_2") (pintype "passive"))
      (node (ref "R23") (pin "2") (pinfunction "2_2") (pintype "passive"))
      (node (ref "R25") (pin "2") (pinfunction "2_2") (pintype "passive"))
      (node (ref "R26") (pin "2") (pinfunction "2_2") (pintype "passive"))
      (node (ref "R9") (pin "2") (pinfunction "2_2") (pintype "passive"))
      (node (ref "S2") (pin "1") (pinfunction "1_1") (pintype "passive"))
      (node (ref "U1") (pin "12") (pinfunction "VSSA_12") (pintype "power_in"))
      (node (ref "U1") (pin "18") (pinfunction "VSS_18") (pintype "power_in"))
      (node (ref "U1") (pin "63") (pinfunction "VSS_63") (pintype "power_in"))
      (node (ref "U10") (pin "2") (pinfunction "GND_2") (pintype "power_in"))
      (node (ref "U2") (pin "3") (pinfunction "VSS_3") (pintype "power_in"))
      (node (ref "U3") (pin "11") (pinfunction "VSS_11") (pintype "power_in"))
      (node (ref "U3") (pin "29") (pinfunction "EP_29") (pintype "passive"))
      (node (ref "U4") (pin "11") (pinfunction "VSS_11") (pintype "power_in"))
      (node (ref "U4") (pin "29") (pinfunction "EP_29") (pintype "passive"))
      (node (ref "U5") (pin "14") (pinfunction "VSS_14") (pintype "power_in"))
      (node (ref "U5") (pin "17") (pinfunction "VSS_17") (pintype "power_in"))
      (node (ref "U5") (pin "20") (pinfunction "VSS_20") (pintype "power_in"))
      (node (ref "U5") (pin "8") (pinfunction "VSS_8") (pintype "power_in"))
      (node (ref "U6") (pin "2") (pinfunction "GND_2") (pintype "passive"))
      (node (ref "U6") (pin "7") (pinfunction "GND_7") (pintype "passive"))
      (node (ref "U7") (pin "2") (pinfunction "INTVCC_2") (pintype "power_in"))
      (node (ref "U7") (pin "4") (pinfunction "ADR0_4") (pintype "input"))
      (node (ref "U7") (pin "5") (pinfunction "ADIN_5") (pintype "input"))
      (node (ref "U7") (pin "6") (pinfunction "GND_6") (pintype "power_in"))
      (node (ref "U8") (pin "1") (pinfunction "CLKIN_1") (pintype "input"))
      (node (ref "U8") (pin "11") (pinfunction "FSYNC_11") (pintype "input"))
      (node (ref "U8") (pin "18") (pinfunction "GND_18") (pintype "power_in"))
      (node (ref "U8") (pin "25") (pinfunction "EP_25") (pintype "power_in"))
      (node (ref "U8") (pin "9") (pinfunction "AD0_9") (pintype "input"))
      (node (ref "U9") (pin "1") (pinfunction "Ground_1") (pintype "power_in"))
      (node (ref "Y1") (pin "2") (pinfunction "GND&Lid_2") (pintype "passive"))
      (node (ref "Y1") (pin "4") (pinfunction "GND&Lid_4") (pintype "passive"))
      (node (ref "Y2") (pin "2") (pinfunction "GND&Lid_2") (pintype "passive"))
      (node (ref "Y2") (pin "4") (pinfunction "GND&Lid_4") (pintype "passive"))
    )
    (net (code "97") (name "Net-(C3-Pad1)") (class "Default")
      (node (ref "C3") (pin "1") (pinfunction "1_1") (pintype "passive"))
      (node (ref "S1") (pin "2") (pinfunction "2_2") (pintype "passive"))
    )
    (net (code "98") (name "Net-(C6-Pad1)") (class "Default")
      (node (ref "C6") (pin "1") (pinfunction "1_1") (pintype "passive"))
      (node (ref "C7") (pin "2") (pinfunction "2_2") (pintype "passive"))
      (node (ref "J39") (pin "1") (pinfunction "1_1") (pintype "passive"))
    )
    (net (code "99") (name "Net-(C6-Pad2)") (class "Default")
      (node (ref "C6") (pin "2") (pinfunction "2_2") (pintype "passive"))
      (node (ref "L1") (pin "2") (pinfunction "2_2") (pintype "passive"))
    )
    (net (code "100") (name "Net-(C11-Pad1)") (class "Default")
      (node (ref "C11") (pin "1") (pinfunction "1_1") (pintype "passive"))
      (node (ref "R22") (pin "1") (pinfunction "1_1") (pintype "passive"))
      (node (ref "Y2") (pin "1") (pinfunction "Crystal_1") (pintype "passive"))
    )
    (net (code "101") (name "Net-(C21-Pad2)") (class "Default")
      (node (ref "C21") (pin "2") (pinfunction "2_2") (pintype "passive"))
      (node (ref "F2") (pin "2") (pinfunction "2_2") (pintype "passive"))
      (node (ref "U9") (pin "2") (pinfunction "VOUT_2") (pintype "passive"))
      (node (ref "U9") (pin "4") (pinfunction "VOUT_4") (pintype "passive"))
    )
    (net (code "102") (name "Net-(D1-Pad2)") (class "Default")
      (node (ref "D1") (pin "2") (pinfunction "2_2") (pintype "passive"))
      (node (ref "R25") (pin "1") (pinfunction "1_1") (pintype "passive"))
    )
    (net (code "103") (name "Net-(F1-Pad2)") (class "Default")
      (node (ref "F1") (pin "2") (pinfunction "2_2") (pintype "passive"))
      (node (ref "J33") (pin "1") (pinfunction "1_1") (pintype "passive"))
    )
    (net (code "104") (name "Net-(S2-C)") (class "Default")
      (node (ref "R8") (pin "2") (pinfunction "2_2") (pintype "passive"))
      (node (ref "S2") (pin "2") (pinfunction "C_2") (pintype "passive"))
    )
    (net (code "105") (name "unconnected-(J34-SHLD1-Pad6)") (class "Default")
      (node (ref "J34") (pin "6") (pinfunction "SHLD1_6") (pintype "passive+no_connect"))
    )
    (net (code "106") (name "unconnected-(J34-SHLD2-Pad7)") (class "Default")
      (node (ref "J34") (pin "7") (pinfunction "SHLD2_7") (pintype "passive+no_connect"))
    )
    (net (code "107") (name "unconnected-(J34-SHLD3-Pad8)") (class "Default")
      (node (ref "J34") (pin "8") (pinfunction "SHLD3_8") (pintype "passive+no_connect"))
    )
    (net (code "108") (name "unconnected-(J34-SHLD4-Pad9)") (class "Default")
      (node (ref "J34") (pin "9") (pinfunction "SHLD4_9") (pintype "passive+no_connect"))
    )
    (net (code "109") (name "unconnected-(J34-SHLD5-Pad10)") (class "Default")
      (node (ref "J34") (pin "10") (pinfunction "SHLD5_10") (pintype "passive+no_connect"))
    )
    (net (code "110") (name "unconnected-(J34-SHLD6-Pad11)") (class "Default")
      (node (ref "J34") (pin "11") (pinfunction "SHLD6_11") (pintype "passive+no_connect"))
    )
    (net (code "111") (name "unconnected-(J34-VBUS-Pad1)") (class "Default")
      (node (ref "J34") (pin "1") (pinfunction "VBUS_1") (pintype "passive+no_connect"))
    )
    (net (code "112") (name "unconnected-(P1-Pad1)") (class "Default")
      (node (ref "P1") (pin "1") (pinfunction "1_1") (pintype "passive"))
    )
    (net (code "113") (name "unconnected-(P1-Pad2)") (class "Default")
      (node (ref "P1") (pin "2") (pinfunction "2_2") (pintype "passive"))
    )
    (net (code "114") (name "unconnected-(P1-Pad3)") (class "Default")
      (node (ref "P1") (pin "3") (pinfunction "3_3") (pintype "passive"))
    )
    (net (code "115") (name "unconnected-(P1-Pad4)") (class "Default")
      (node (ref "P1") (pin "4") (pinfunction "4_4") (pintype "passive"))
    )
    (net (code "116") (name "unconnected-(P1-Pad5)") (class "Default")
      (node (ref "P1") (pin "5") (pinfunction "5_5") (pintype "passive"))
    )
    (net (code "117") (name "unconnected-(P1-Pad6)") (class "Default")
      (node (ref "P1") (pin "6") (pinfunction "6_6") (pintype "passive"))
    )
    (net (code "118") (name "unconnected-(P1-Pad7)") (class "Default")
      (node (ref "P1") (pin "7") (pinfunction "7_7") (pintype "passive"))
    )
    (net (code "119") (name "unconnected-(P1-Pad8)") (class "Default")
      (node (ref "P1") (pin "8") (pinfunction "8_8") (pintype "passive"))
    )
    (net (code "120") (name "unconnected-(S1-Pad1)") (class "Default")
      (node (ref "S1") (pin "1") (pinfunction "1_1") (pintype "passive"))
    )
    (net (code "121") (name "unconnected-(S1-Pad4)") (class "Default")
      (node (ref "S1") (pin "4") (pinfunction "4_4") (pintype "passive"))
    )
    (net (code "122") (name "unconnected-(S2-MNT_1-Pad4)") (class "Default")
      (node (ref "S2") (pin "4") (pinfunction "MNT_1_4") (pintype "passive+no_connect"))
    )
    (net (code "123") (name "unconnected-(S2-MNT_2-Pad5)") (class "Default")
      (node (ref "S2") (pin "5") (pinfunction "MNT_2_5") (pintype "passive+no_connect"))
    )
    (net (code "124") (name "unconnected-(U1A-PA9-Pad42)") (class "Default")
      (node (ref "U1") (pin "42") (pinfunction "PA9_42") (pintype "bidirectional+no_connect"))
    )
    (net (code "125") (name "unconnected-(U1A-PB0-Pad26)") (class "Default")
      (node (ref "U1") (pin "26") (pinfunction "PB0_26") (pintype "bidirectional+no_connect"))
    )
    (net (code "126") (name "unconnected-(U1A-PB1-Pad27)") (class "Default")
      (node (ref "U1") (pin "27") (pinfunction "PB1_27") (pintype "bidirectional+no_connect"))
    )
    (net (code "127") (name "unconnected-(U1A-PB4(NJTRST)-Pad56)") (class "Default")
      (node (ref "U1") (pin "56") (pinfunction "PB4(NJTRST)_56") (pintype "bidirectional+no_connect"))
    )
    (net (code "128") (name "unconnected-(U1A-PB5-Pad57)") (class "Default")
      (node (ref "U1") (pin "57") (pinfunction "PB5_57") (pintype "bidirectional+no_connect"))
    )
    (net (code "129") (name "unconnected-(U1A-PB8-Pad61)") (class "Default")
      (node (ref "U1") (pin "61") (pinfunction "PB8_61") (pintype "bidirectional+no_connect"))
    )
    (net (code "130") (name "unconnected-(U1A-PB9-Pad62)") (class "Default")
      (node (ref "U1") (pin "62") (pinfunction "PB9_62") (pintype "bidirectional+no_connect"))
    )
    (net (code "131") (name "unconnected-(U1A-PB12-Pad33)") (class "Default")
      (node (ref "U1") (pin "33") (pinfunction "PB12_33") (pintype "bidirectional+no_connect"))
    )
    (net (code "132") (name "unconnected-(U1A-PB14-Pad35)") (class "Default")
      (node (ref "U1") (pin "35") (pinfunction "PB14_35") (pintype "bidirectional+no_connect"))
    )
    (net (code "133") (name "unconnected-(U1A-PB15-Pad36)") (class "Default")
      (node (ref "U1") (pin "36") (pinfunction "PB15_36") (pintype "bidirectional+no_connect"))
    )
    (net (code "134") (name "unconnected-(U1A-PC0-Pad8)") (class "Default")
      (node (ref "U1") (pin "8") (pinfunction "PC0_8") (pintype "bidirectional+no_connect"))
    )
    (net (code "135") (name "unconnected-(U1A-PC4-Pad24)") (class "Default")
      (node (ref "U1") (pin "24") (pinfunction "PC4_24") (pintype "bidirectional+no_connect"))
    )
    (net (code "136") (name "unconnected-(U1A-PC5-Pad25)") (class "Default")
      (node (ref "U1") (pin "25") (pinfunction "PC5_25") (pintype "bidirectional+no_connect"))
    )
    (net (code "137") (name "unconnected-(U1A-PC6-Pad37)") (class "Default")
      (node (ref "U1") (pin "37") (pinfunction "PC6_37") (pintype "bidirectional+no_connect"))
    )
    (net (code "138") (name "unconnected-(U1A-PC7-Pad38)") (class "Default")
      (node (ref "U1") (pin "38") (pinfunction "PC7_38") (pintype "bidirectional+no_connect"))
    )
    (net (code "139") (name "unconnected-(U1A-PC10-Pad51)") (class "Default")
      (node (ref "U1") (pin "51") (pinfunction "PC10_51") (pintype "bidirectional+no_connect"))
    )
    (net (code "140") (name "unconnected-(U1A-PC11-Pad52)") (class "Default")
      (node (ref "U1") (pin "52") (pinfunction "PC11_52") (pintype "bidirectional+no_connect"))
    )
    (net (code "141") (name "unconnected-(U1A-PC12-Pad53)") (class "Default")
      (node (ref "U1") (pin "53") (pinfunction "PC12_53") (pintype "bidirectional+no_connect"))
    )
    (net (code "142") (name "unconnected-(U1A-PC13-Pad2)") (class "Default")
      (node (ref "U1") (pin "2") (pinfunction "PC13_2") (pintype "bidirectional+no_connect"))
    )
    (net (code "143") (name "unconnected-(U1A-PC14-OSC32_IN(PC14)-Pad3)") (class "Default")
      (node (ref "U1") (pin "3") (pinfunction "PC14-OSC32_IN(PC14)_3") (pintype "bidirectional+no_connect"))
    )
    (net (code "144") (name "unconnected-(U1A-PC15-OSC32_OUT(PC15)-Pad4)") (class "Default")
      (node (ref "U1") (pin "4") (pinfunction "PC15-OSC32_OUT(PC15)_4") (pintype "bidirectional+no_connect"))
    )
    (net (code "145") (name "unconnected-(U1A-PD2-Pad54)") (class "Default")
      (node (ref "U1") (pin "54") (pinfunction "PD2_54") (pintype "bidirectional+no_connect"))
    )
    (net (code "146") (name "unconnected-(U1B-VBAT-Pad1)") (class "Default")
      (node (ref "U1") (pin "1") (pinfunction "VBAT_1") (pintype "power_in"))
    )
    (net (code "147") (name "unconnected-(U2-DOUT-Pad2)") (class "Default")
      (node (ref "U2") (pin "2") (pinfunction "DOUT_2") (pintype "output+no_connect"))
    )
    (net (code "148") (name "unconnected-(U3-EXTCLK-Pad22)") (class "Default")
      (node (ref "U3") (pin "22") (pinfunction "EXTCLK_22") (pintype "input+no_connect"))
    )
    (net (code "149") (name "unconnected-(U4-EXTCLK-Pad22)") (class "Default")
      (node (ref "U4") (pin "22") (pinfunction "EXTCLK_22") (pintype "input+no_connect"))
    )
    (net (code "150") (name "unconnected-(U8-AUX_CL-Pad7)") (class "Default")
      (node (ref "U8") (pin "7") (pinfunction "AUX_CL_7") (pintype "output+no_connect"))
    )
    (net (code "151") (name "unconnected-(U8-AUX_DA-Pad6)") (class "Default")
      (node (ref "U8") (pin "6") (pinfunction "AUX_DA_6") (pintype "bidirectional+no_connect"))
    )
    (net (code "152") (name "unconnected-(U8-CLKOUT-Pad22)") (class "Default")
      (node (ref "U8") (pin "22") (pinfunction "CLKOUT_22") (pintype "output+no_connect"))
    )
    (net (code "153") (name "unconnected-(U8-NC-Pad2)") (class "Default")
      (node (ref "U8") (pin "2") (pinfunction "NC_2") (pintype "passive+no_connect"))
    )
    (net (code "154") (name "unconnected-(U8-NC-Pad3)") (class "Default")
      (node (ref "U8") (pin "3") (pinfunction "NC_3") (pintype "passive+no_connect"))
    )
    (net (code "155") (name "unconnected-(U8-NC-Pad4)") (class "Default")
      (node (ref "U8") (pin "4") (pinfunction "NC_4") (pintype "passive+no_connect"))
    )
    (net (code "156") (name "unconnected-(U8-NC-Pad5)") (class "Default")
      (node (ref "U8") (pin "5") (pinfunction "NC_5") (pintype "passive+no_connect"))
    )
    (net (code "157") (name "unconnected-(U8-NC-Pad14)") (class "Default")
      (node (ref "U8") (pin "14") (pinfunction "NC_14") (pintype "passive+no_connect"))
    )
    (net (code "158") (name "unconnected-(U8-NC-Pad15)") (class "Default")
      (node (ref "U8") (pin "15") (pinfunction "NC_15") (pintype "passive+no_connect"))
    )
    (net (code "159") (name "unconnected-(U8-NC-Pad16)") (class "Default")
      (node (ref "U8") (pin "16") (pinfunction "NC_16") (pintype "passive+no_connect"))
    )
    (net (code "160") (name "unconnected-(U8-NC-Pad17)") (class "Default")
      (node (ref "U8") (pin "17") (pinfunction "NC_17") (pintype "passive+no_connect"))
    )
    (net (code "161") (name "unconnected-(U8-RESV-Pad19)") (class "Default")
      (node (ref "U8") (pin "19") (pinfunction "RESV_19") (pintype "passive+no_connect"))
    )
    (net (code "162") (name "unconnected-(U8-RESV-Pad21)") (class "Default")
      (node (ref "U8") (pin "21") (pinfunction "RESV_21") (pintype "passive+no_connect"))
    )
  )
)
